# controller.net
KiCad netlist of a schematic drawn in EAGLE
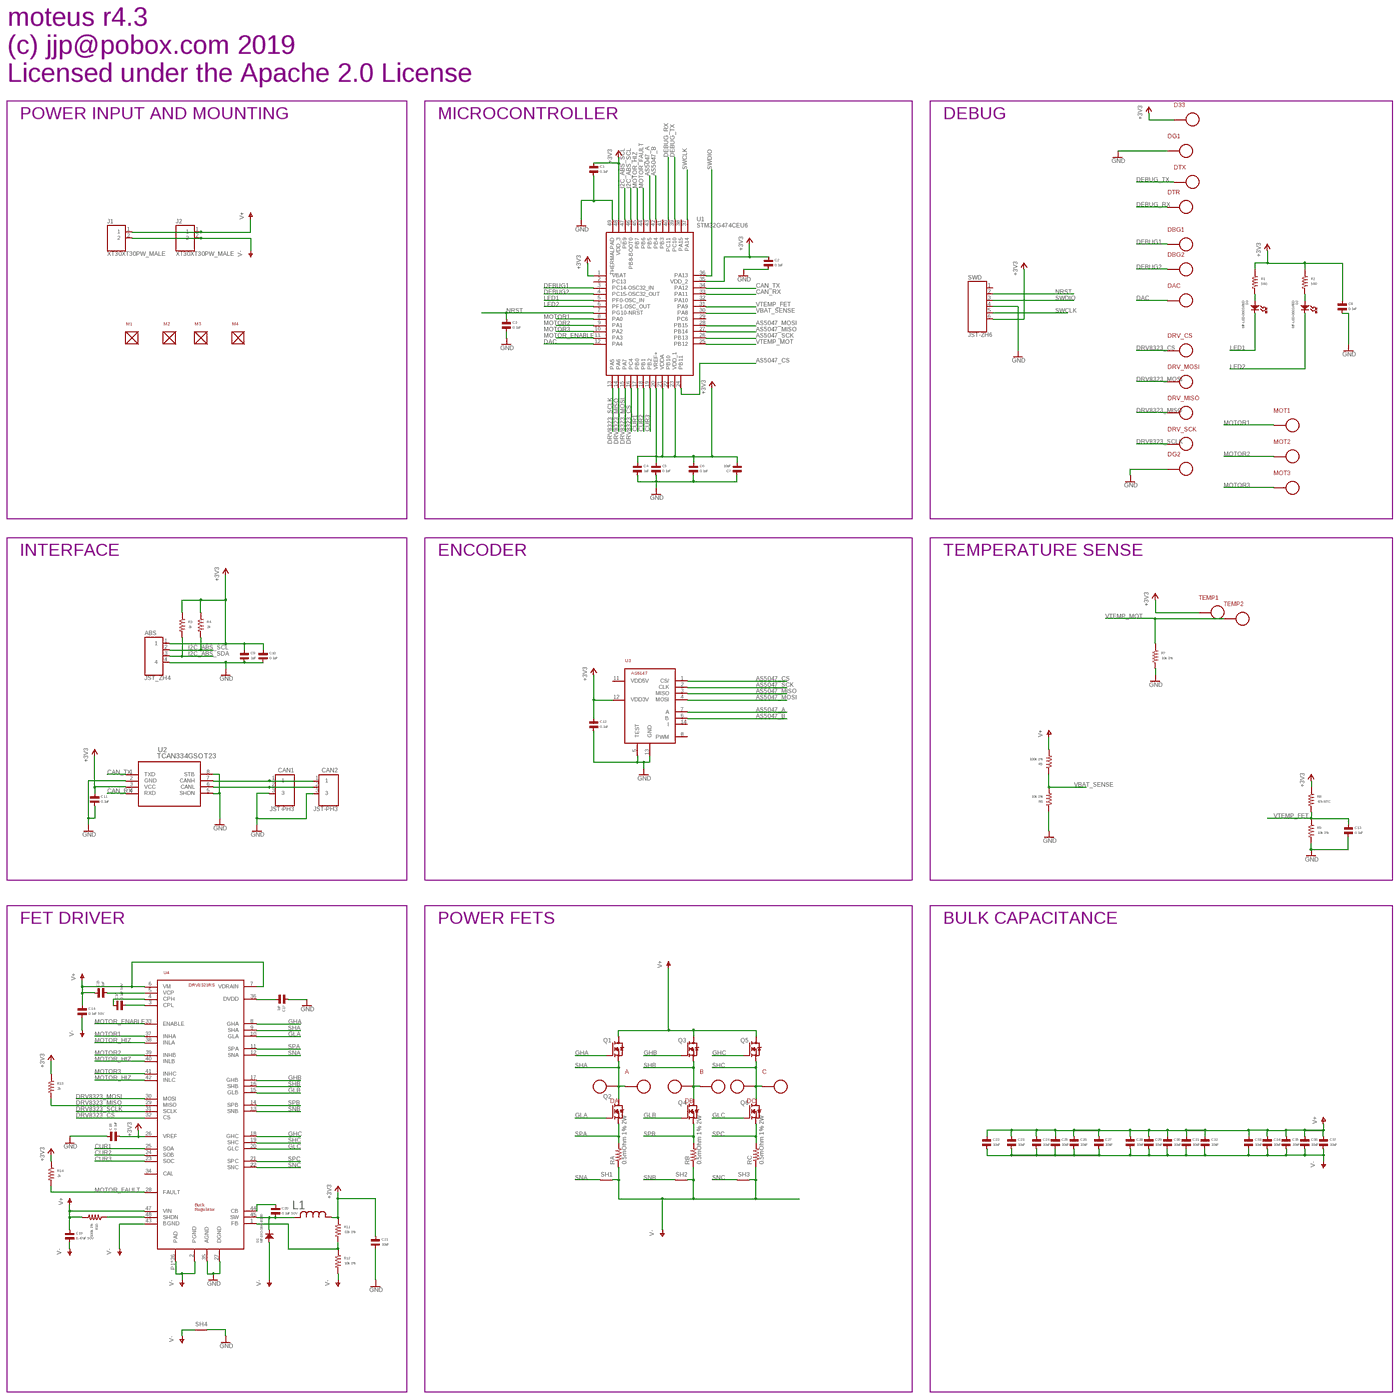
[diagram p0: schematic, sheet 1, overview]
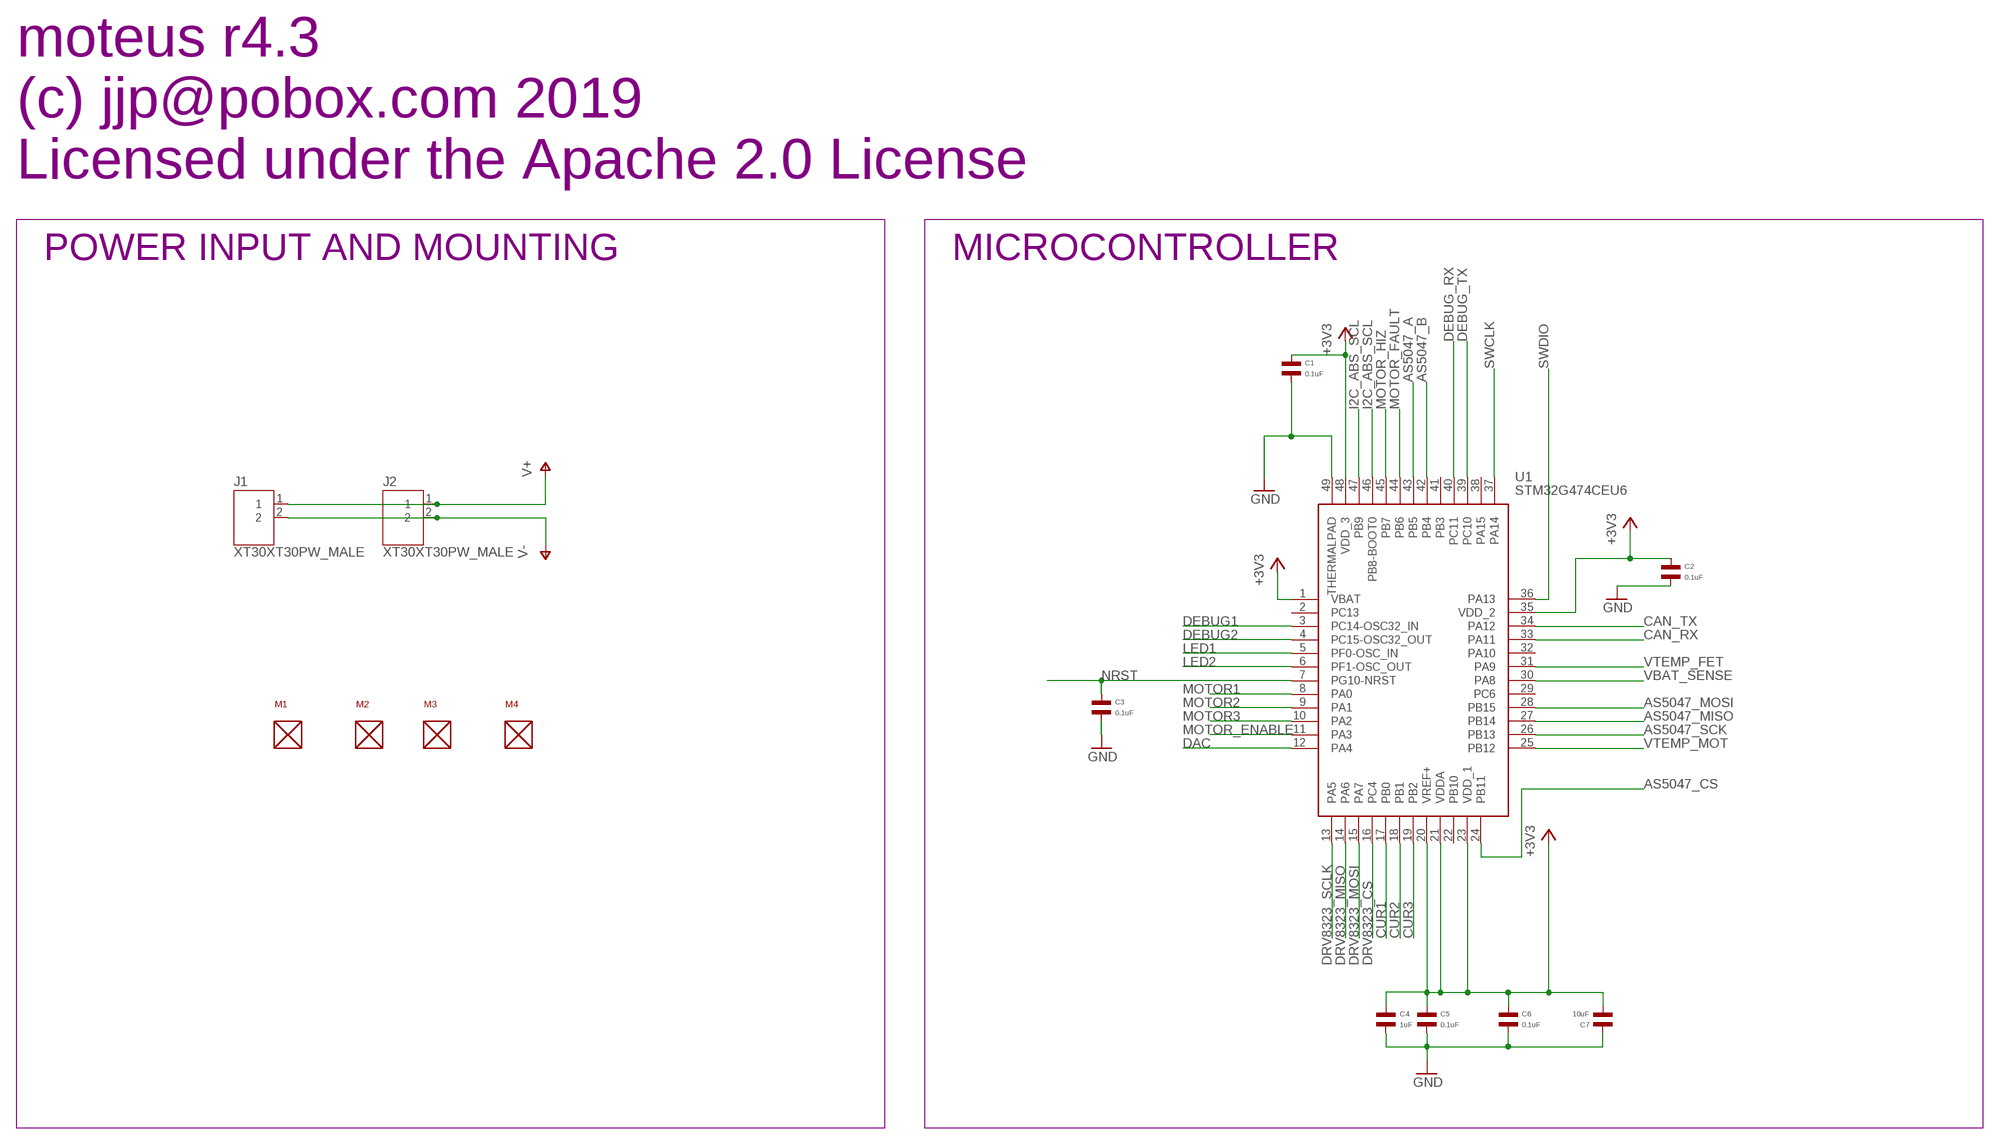
[diagram p1: schematic, sheet 1, part 1 of 4]
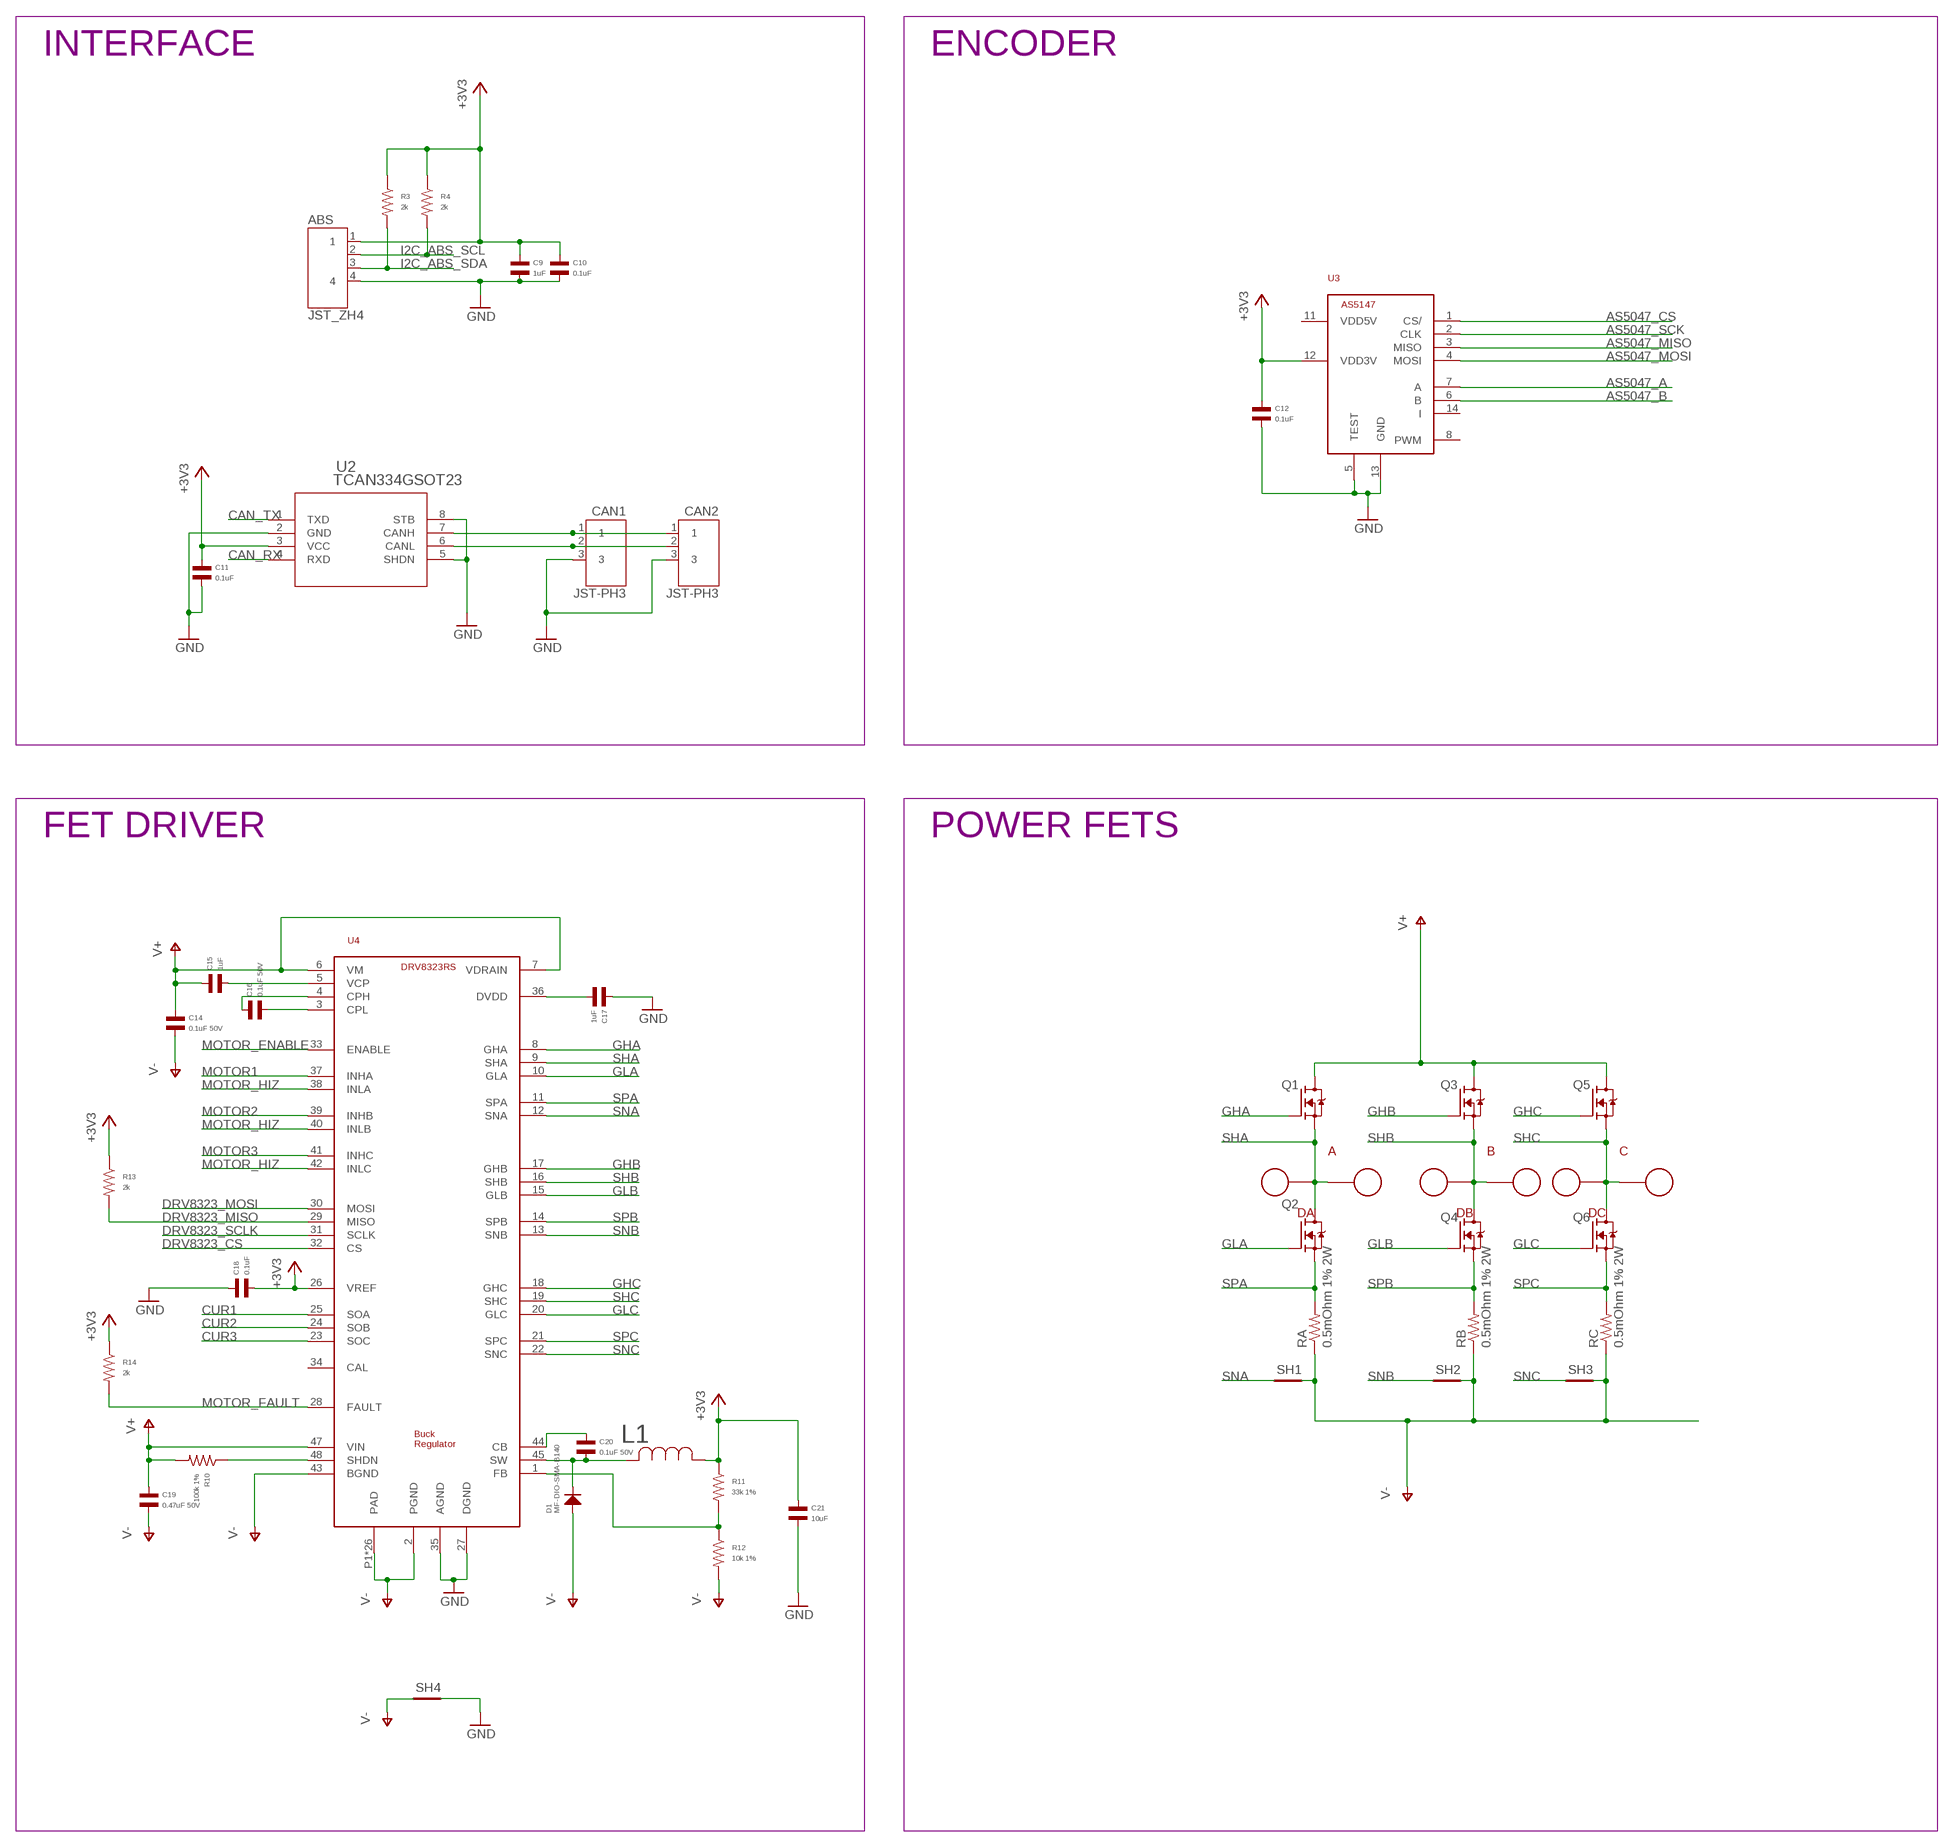
[diagram p2: schematic, sheet 1, part 2 of 4]
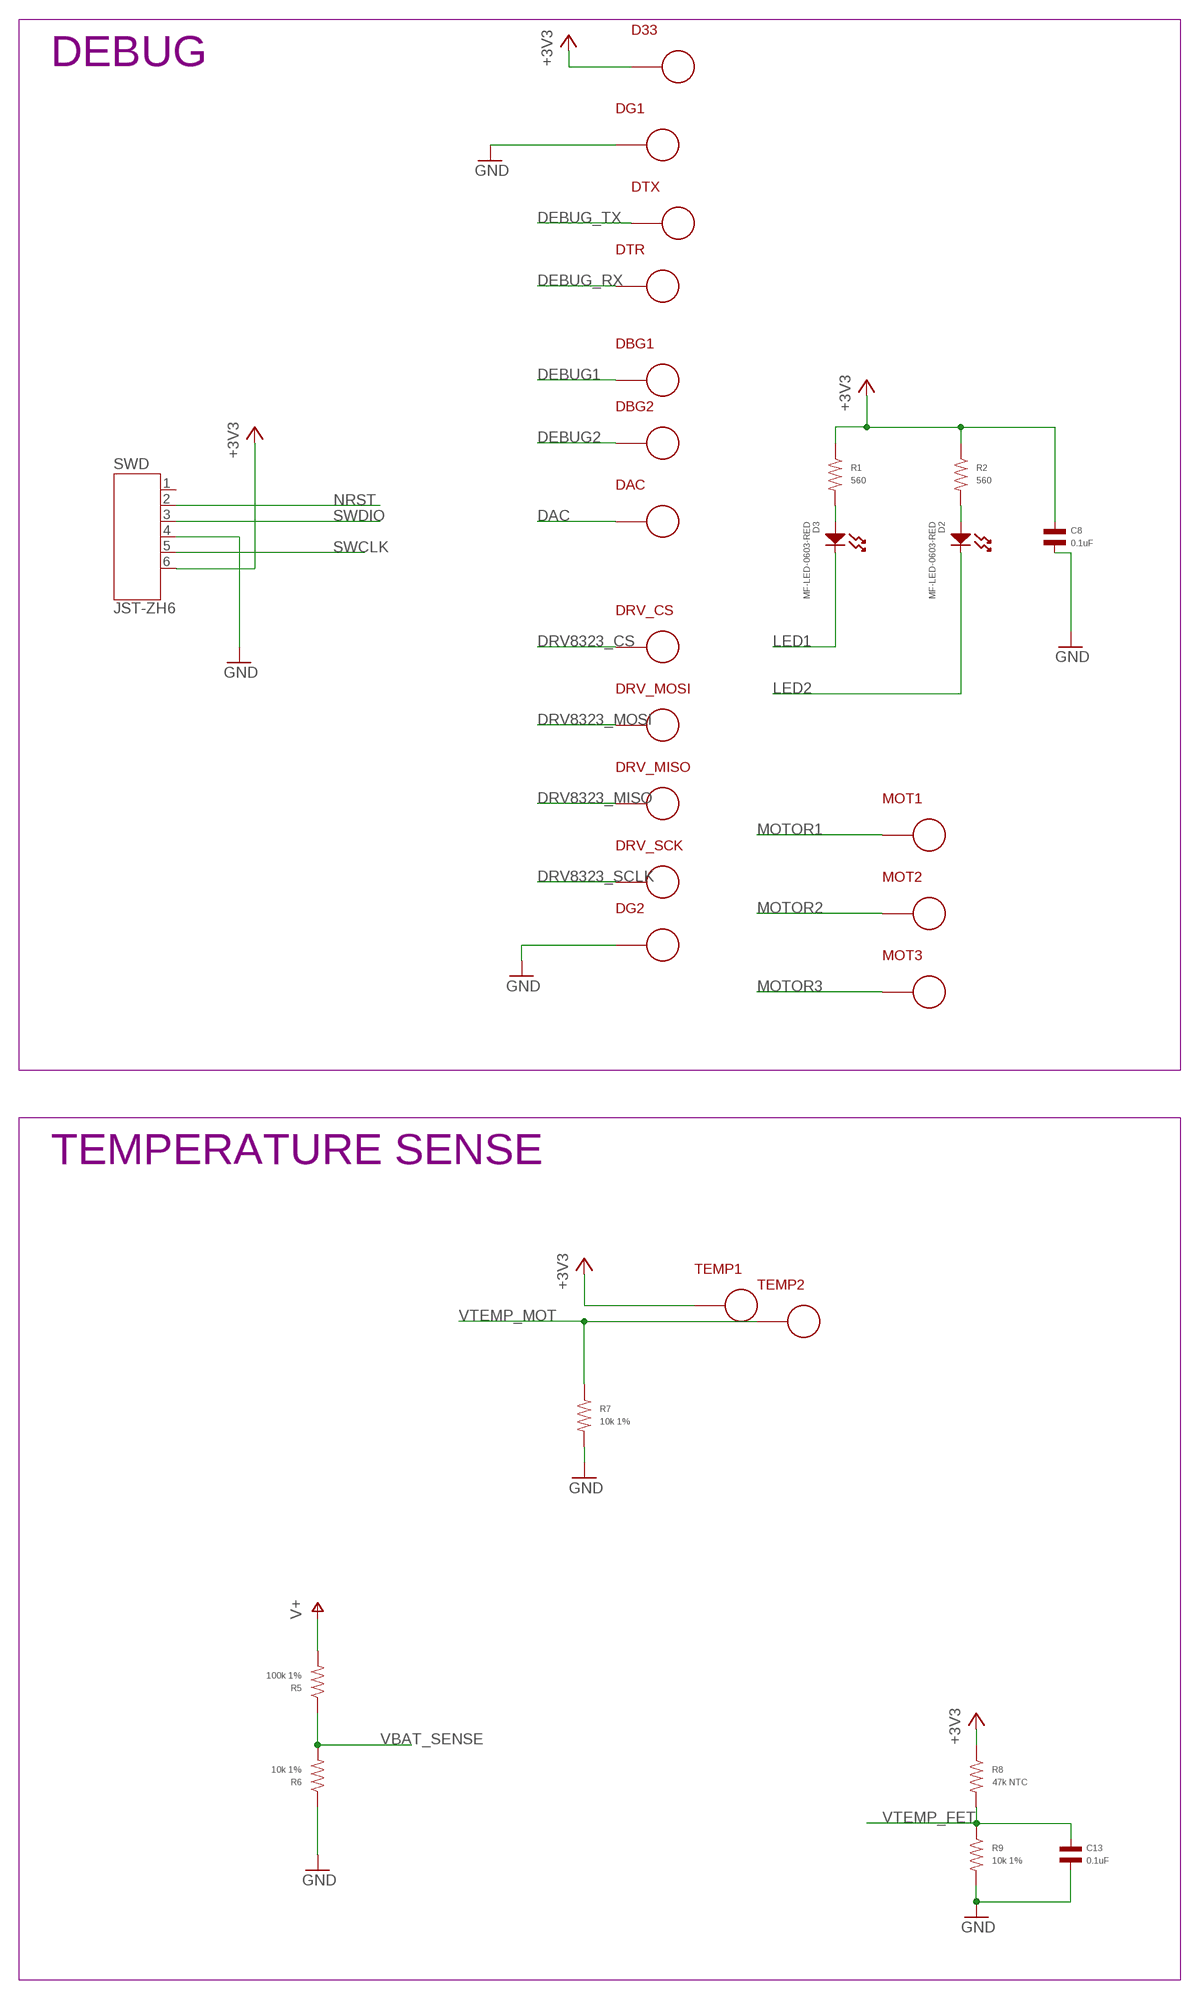
[diagram p3: schematic, sheet 1, part 3 of 4]
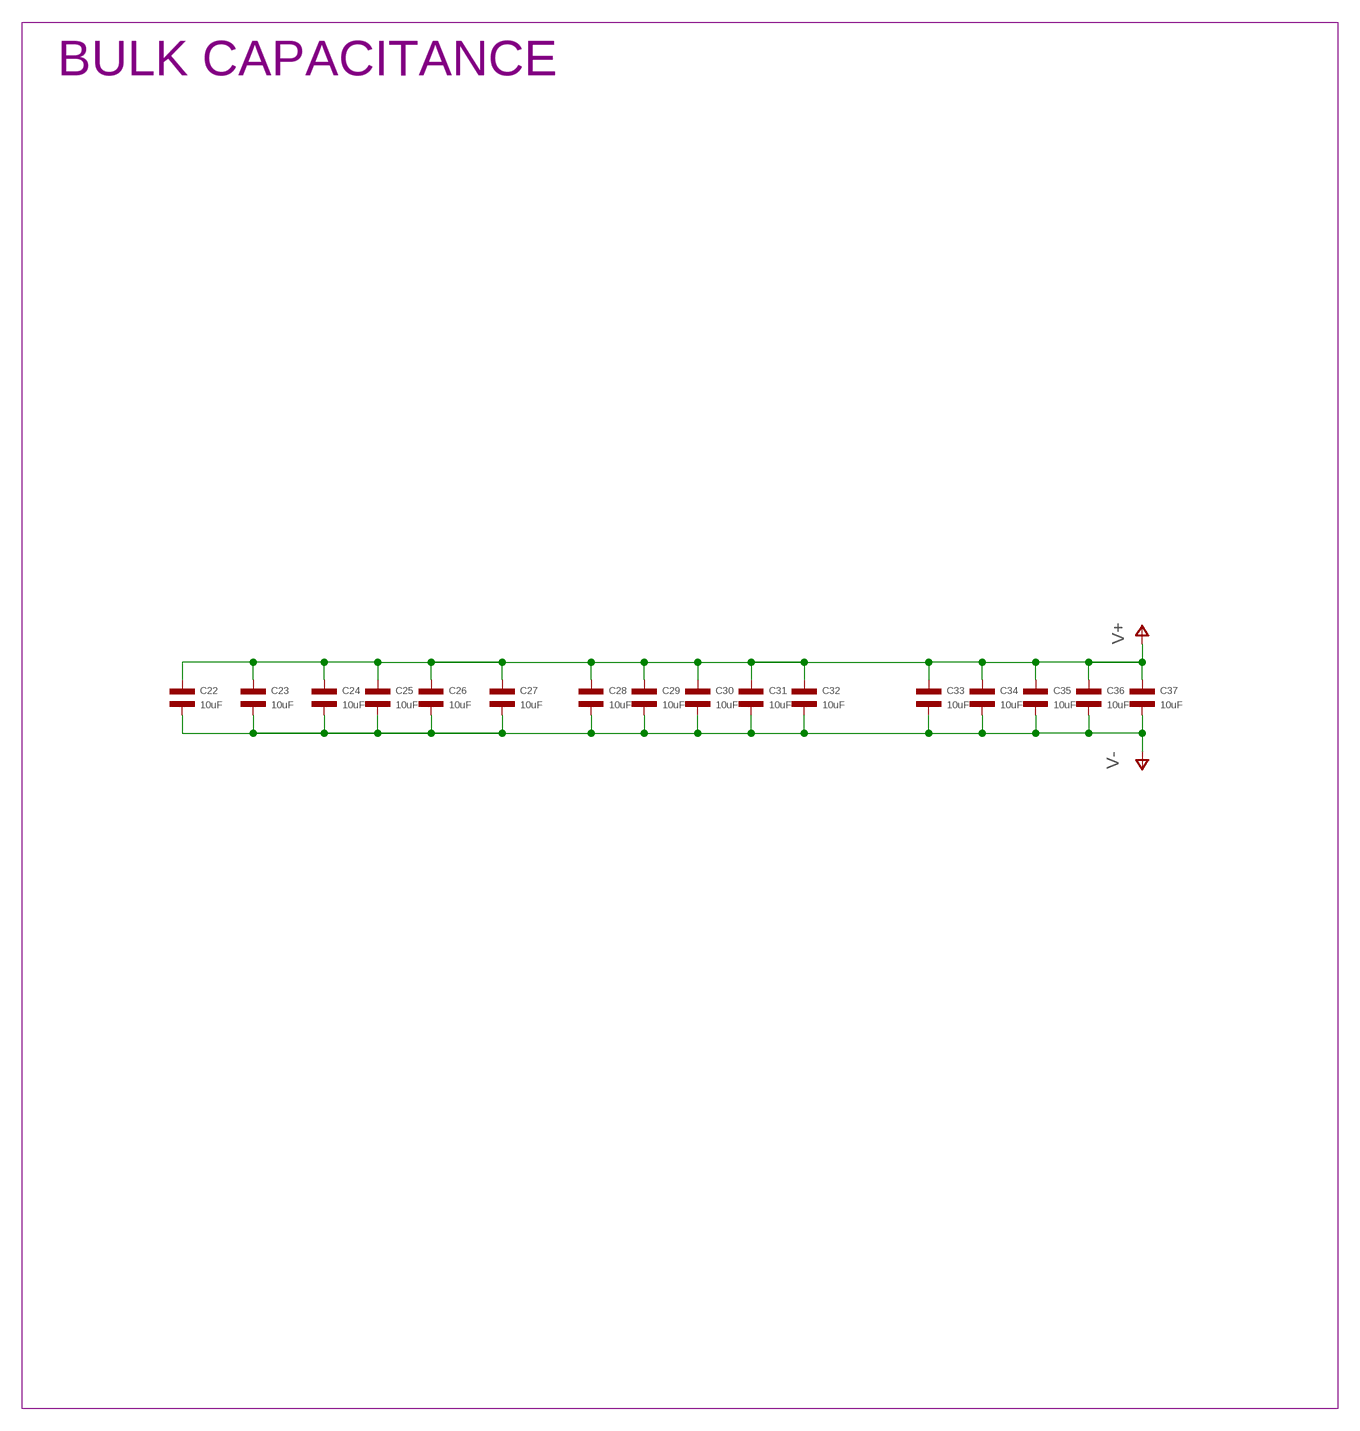
[diagram p4: schematic, sheet 1, part 4 of 4]

(export (version "E")
  (design (tool "Eeschema 10.0.6"))
  (components
    (comp (ref "A")
      (value "PAD")
      (footprint "eagle-import:18AWG_PAD")
      (libsource (lib "eagle-import") (part "PAD"))
    )
    (comp (ref "ABS")
      (value "JST_ZH4")
      (footprint "eagle-import:JST_S4B-ZR-SM4A-TF(LF)(SN)")
      (fields (field (name "MF") "JST") (field (name "MPN") "S4B-ZR-SM4A-TF(LF)(SN)"))
      (libsource (lib "eagle-import") (part "JST_ZH4"))
    )
    (comp (ref "B")
      (value "PAD")
      (footprint "eagle-import:18AWG_PAD")
      (libsource (lib "eagle-import") (part "PAD"))
    )
    (comp (ref "C")
      (value "PAD")
      (footprint "eagle-import:18AWG_PAD")
      (libsource (lib "eagle-import") (part "PAD"))
    )
    (comp (ref "C1")
      (value "0.1uF")
      (footprint "eagle-import:C0402")
      (fields (field (name "HOUSEPART") "YES") (field (name "MPN") "MF-CAP-0402-0.1uF"))
      (libsource (lib "eagle-import") (part "CAPACITOR_NP_0402"))
    )
    (comp (ref "C2")
      (value "0.1uF")
      (footprint "eagle-import:C0402")
      (fields (field (name "HOUSEPART") "YES") (field (name "MPN") "MF-CAP-0402-0.1uF"))
      (libsource (lib "eagle-import") (part "CAPACITOR_NP_0402"))
    )
    (comp (ref "C3")
      (value "0.1uF")
      (footprint "eagle-import:C0402")
      (fields (field (name "HOUSEPART") "YES") (field (name "MPN") "MF-CAP-0402-0.1uF"))
      (libsource (lib "eagle-import") (part "CAPACITOR_NP_0402"))
    )
    (comp (ref "C4")
      (value "1uF")
      (footprint "eagle-import:C0402")
      (fields (field (name "HOUSEPART") "YES") (field (name "MPN") "MF-CAP-0402-1uF"))
      (libsource (lib "eagle-import") (part "CAPACITOR_NP_0402"))
    )
    (comp (ref "C5")
      (value "0.1uF")
      (footprint "eagle-import:C0402")
      (fields (field (name "HOUSEPART") "YES") (field (name "MPN") "MF-CAP-0402-0.1uF"))
      (libsource (lib "eagle-import") (part "CAPACITOR_NP_0402"))
    )
    (comp (ref "C6")
      (value "0.1uF")
      (footprint "eagle-import:C0402")
      (fields (field (name "HOUSEPART") "YES") (field (name "MPN") "MF-CAP-0402-0.1uF"))
      (libsource (lib "eagle-import") (part "CAPACITOR_NP_0402"))
    )
    (comp (ref "C7")
      (value "10uF")
      (footprint "eagle-import:C1206")
      (fields (field (name "HOUSEPART") "YES") (field (name "MPN") "MF-CAP-1206-10uF"))
      (libsource (lib "eagle-import") (part "CAPACITOR_NP_1206"))
    )
    (comp (ref "C8")
      (value "0.1uF")
      (footprint "eagle-import:C0402")
      (fields (field (name "HOUSEPART") "YES") (field (name "MPN") "MF-CAP-0402-0.1uF"))
      (libsource (lib "eagle-import") (part "CAPACITOR_NP_0402"))
    )
    (comp (ref "C9")
      (value "1uF")
      (footprint "eagle-import:C0402")
      (fields (field (name "HOUSEPART") "YES") (field (name "MPN") "MF-CAP-0402-1uF"))
      (libsource (lib "eagle-import") (part "CAPACITOR_NP_0402"))
    )
    (comp (ref "C10")
      (value "0.1uF")
      (footprint "eagle-import:C0402")
      (fields (field (name "HOUSEPART") "YES") (field (name "MPN") "MF-CAP-0402-0.1uF"))
      (libsource (lib "eagle-import") (part "CAPACITOR_NP_0402"))
    )
    (comp (ref "C11")
      (value "0.1uF")
      (footprint "eagle-import:C0402")
      (fields (field (name "HOUSEPART") "YES") (field (name "MPN") "MF-CAP-0402-0.1uF"))
      (libsource (lib "eagle-import") (part "CAPACITOR_NP_0402"))
    )
    (comp (ref "C12")
      (value "0.1uF")
      (footprint "eagle-import:C0402")
      (fields (field (name "HOUSEPART") "YES") (field (name "MPN") "MF-CAP-0402-0.1uF"))
      (libsource (lib "eagle-import") (part "CAPACITOR_NP_0402"))
    )
    (comp (ref "C13")
      (value "0.1uF")
      (footprint "eagle-import:C0402")
      (fields (field (name "HOUSEPART") "YES") (field (name "MPN") "MF-CAP-0402-0.1uF"))
      (libsource (lib "eagle-import") (part "CAPACITOR_NP_0402"))
    )
    (comp (ref "C14")
      (value "0.1uF 50V")
      (footprint "eagle-import:C0402")
      (fields (field (name "MF") "TDK") (field (name "MPN") "CGA2B3X7R1H104K050BB"))
      (libsource (lib "eagle-import") (part "CAPACITOR_NP_0402"))
    )
    (comp (ref "C15")
      (value "1uF")
      (footprint "eagle-import:C0402")
      (fields (field (name "HOUSEPART") "YES") (field (name "MPN") "MF-CAP-0402-1uF"))
      (libsource (lib "eagle-import") (part "CAPACITOR_NP_0402"))
    )
    (comp (ref "C16")
      (value "0.1uF 50V")
      (footprint "eagle-import:C0402")
      (fields (field (name "MF") "TDK") (field (name "MPN") "CGA2B3X7R1H104K050BB"))
      (libsource (lib "eagle-import") (part "CAPACITOR_NP_0402"))
    )
    (comp (ref "C17")
      (value "1uF")
      (footprint "eagle-import:C0402")
      (fields (field (name "HOUSEPART") "YES") (field (name "MPN") "MF-CAP-0402-1uF"))
      (libsource (lib "eagle-import") (part "CAPACITOR_NP_0402"))
    )
    (comp (ref "C18")
      (value "0.1uF")
      (footprint "eagle-import:C0402")
      (fields (field (name "HOUSEPART") "YES") (field (name "MPN") "MF-CAP-0402-0.1uF"))
      (libsource (lib "eagle-import") (part "CAPACITOR_NP_0402"))
    )
    (comp (ref "C19")
      (value "0.47uF 50V")
      (footprint "eagle-import:C0402")
      (fields (field (name "MF") "Taiyo Yuden") (field (name "MPN") "UMK105ABJ474KV-F"))
      (libsource (lib "eagle-import") (part "CAPACITOR_NP_0402"))
    )
    (comp (ref "C20")
      (value "0.1uF 50V")
      (footprint "eagle-import:C0402")
      (fields (field (name "MF") "TDK") (field (name "MPN") "CGA2B3X7R1H104K050BB"))
      (libsource (lib "eagle-import") (part "CAPACITOR_NP_0402"))
    )
    (comp (ref "C21")
      (value "10uF")
      (footprint "eagle-import:C1206")
      (fields (field (name "HOUSEPART") "YES") (field (name "MPN") "MF-CAP-1206-10uF"))
      (libsource (lib "eagle-import") (part "CAPACITOR_NP_1206"))
    )
    (comp (ref "C22")
      (value "10uF")
      (footprint "eagle-import:C1206")
      (fields (field (name "MF") "TDK") (field (name "MPN") "CGA5L1X7R1H106K160AC"))
      (libsource (lib "eagle-import") (part "CAPACITOR_NP_1206"))
    )
    (comp (ref "C23")
      (value "10uF")
      (footprint "eagle-import:C1206")
      (fields (field (name "MF") "TDK") (field (name "MPN") "CGA5L1X7R1H106K160AC"))
      (libsource (lib "eagle-import") (part "CAPACITOR_NP_1206"))
    )
    (comp (ref "C24")
      (value "10uF")
      (footprint "eagle-import:C1206")
      (fields (field (name "MF") "TDK") (field (name "MPN") "CGA5L1X7R1H106K160AC"))
      (libsource (lib "eagle-import") (part "CAPACITOR_NP_1206"))
    )
    (comp (ref "C25")
      (value "10uF")
      (footprint "eagle-import:C1206")
      (fields (field (name "MF") "TDK") (field (name "MPN") "CGA5L1X7R1H106K160AC"))
      (libsource (lib "eagle-import") (part "CAPACITOR_NP_1206"))
    )
    (comp (ref "C26")
      (value "10uF")
      (footprint "eagle-import:C1206")
      (fields (field (name "MF") "TDK") (field (name "MPN") "CGA5L1X7R1H106K160AC"))
      (libsource (lib "eagle-import") (part "CAPACITOR_NP_1206"))
    )
    (comp (ref "C27")
      (value "10uF")
      (footprint "eagle-import:C1206")
      (fields (field (name "MF") "TDK") (field (name "MPN") "CGA5L1X7R1H106K160AC"))
      (libsource (lib "eagle-import") (part "CAPACITOR_NP_1206"))
    )
    (comp (ref "C28")
      (value "10uF")
      (footprint "eagle-import:C1206")
      (fields (field (name "MF") "TDK") (field (name "MPN") "CGA5L1X7R1H106K160AC"))
      (libsource (lib "eagle-import") (part "CAPACITOR_NP_1206"))
    )
    (comp (ref "C29")
      (value "10uF")
      (footprint "eagle-import:C1206")
      (fields (field (name "MF") "TDK") (field (name "MPN") "CGA5L1X7R1H106K160AC"))
      (libsource (lib "eagle-import") (part "CAPACITOR_NP_1206"))
    )
    (comp (ref "C30")
      (value "10uF")
      (footprint "eagle-import:C1206")
      (fields (field (name "MF") "TDK") (field (name "MPN") "CGA5L1X7R1H106K160AC"))
      (libsource (lib "eagle-import") (part "CAPACITOR_NP_1206"))
    )
    (comp (ref "C31")
      (value "10uF")
      (footprint "eagle-import:C1206")
      (fields (field (name "MF") "TDK") (field (name "MPN") "CGA5L1X7R1H106K160AC"))
      (libsource (lib "eagle-import") (part "CAPACITOR_NP_1206"))
    )
    (comp (ref "C32")
      (value "10uF")
      (footprint "eagle-import:C1206")
      (fields (field (name "MF") "TDK") (field (name "MPN") "CGA5L1X7R1H106K160AC"))
      (libsource (lib "eagle-import") (part "CAPACITOR_NP_1206"))
    )
    (comp (ref "C33")
      (value "10uF")
      (footprint "eagle-import:C1206")
      (fields (field (name "MF") "TDK") (field (name "MPN") "CGA5L1X7R1H106K160AC"))
      (libsource (lib "eagle-import") (part "CAPACITOR_NP_1206"))
    )
    (comp (ref "C34")
      (value "10uF")
      (footprint "eagle-import:C1206")
      (fields (field (name "MF") "TDK") (field (name "MPN") "CGA5L1X7R1H106K160AC"))
      (libsource (lib "eagle-import") (part "CAPACITOR_NP_1206"))
    )
    (comp (ref "C35")
      (value "10uF")
      (footprint "eagle-import:C1206")
      (fields (field (name "MF") "TDK") (field (name "MPN") "CGA5L1X7R1H106K160AC"))
      (libsource (lib "eagle-import") (part "CAPACITOR_NP_1206"))
    )
    (comp (ref "C36")
      (value "10uF")
      (footprint "eagle-import:C1206")
      (fields (field (name "MF") "TDK") (field (name "MPN") "CGA5L1X7R1H106K160AC"))
      (libsource (lib "eagle-import") (part "CAPACITOR_NP_1206"))
    )
    (comp (ref "C37")
      (value "10uF")
      (footprint "eagle-import:C1206")
      (fields (field (name "MF") "TDK") (field (name "MPN") "CGA5L1X7R1H106K160AC"))
      (libsource (lib "eagle-import") (part "CAPACITOR_NP_1206"))
    )
    (comp (ref "CAN1")
      (value "JST-PH3")
      (footprint "eagle-import:JST_S3B-PH-SM4-TB(LF)(SN)")
      (fields (field (name "MF") "JST") (field (name "MPN") "S3B-PH-SM4-TB(LF)(SN)"))
      (libsource (lib "eagle-import") (part "JST-PH3"))
    )
    (comp (ref "CAN2")
      (value "JST-PH3")
      (footprint "eagle-import:JST_S3B-PH-SM4-TB(LF)(SN)")
      (fields (field (name "MF") "JST") (field (name "MPN") "S3B-PH-SM4-TB(LF)(SN)"))
      (libsource (lib "eagle-import") (part "JST-PH3"))
    )
    (comp (ref "D1")
      (value "MF-DIO-SMA-B140")
      (footprint "eagle-import:SMA")
      (fields (field (name "HOUSEPART") "YES"))
      (libsource (lib "eagle-import") (part "DIODES_SMA_B140"))
    )
    (comp (ref "D2")
      (value "MF-LED-0603-RED")
      (footprint "eagle-import:LED0603")
      (fields (field (name "HOUSEPART") "YES") (field (name "MPN") "MF-LED-0603-GREEN"))
      (libsource (lib "eagle-import") (part "LED_SINGLE-0603-RED"))
    )
    (comp (ref "D3")
      (value "MF-LED-0603-RED")
      (footprint "eagle-import:LED0603")
      (fields (field (name "HOUSEPART") "YES"))
      (libsource (lib "eagle-import") (part "LED_SINGLE-0603-RED"))
    )
    (comp (ref "D33")
      (value "PAD24AWG_PAD")
      (footprint "eagle-import:24AWG_PAD")
      (libsource (lib "eagle-import") (part "PAD24AWG_PAD"))
    )
    (comp (ref "DA")
      (value "PAD24AWG_PAD")
      (footprint "eagle-import:24AWG_PAD")
      (libsource (lib "eagle-import") (part "PAD24AWG_PAD"))
    )
    (comp (ref "DAC")
      (value "PAD24AWG_PAD")
      (footprint "eagle-import:24AWG_PAD")
      (libsource (lib "eagle-import") (part "PAD24AWG_PAD"))
    )
    (comp (ref "DB")
      (value "PAD24AWG_PAD")
      (footprint "eagle-import:24AWG_PAD")
      (libsource (lib "eagle-import") (part "PAD24AWG_PAD"))
    )
    (comp (ref "DBG1")
      (value "PAD24AWG_PAD")
      (footprint "eagle-import:24AWG_PAD")
      (libsource (lib "eagle-import") (part "PAD24AWG_PAD"))
    )
    (comp (ref "DBG2")
      (value "PAD24AWG_PAD")
      (footprint "eagle-import:24AWG_PAD")
      (libsource (lib "eagle-import") (part "PAD24AWG_PAD"))
    )
    (comp (ref "DC")
      (value "PAD24AWG_PAD")
      (footprint "eagle-import:24AWG_PAD")
      (libsource (lib "eagle-import") (part "PAD24AWG_PAD"))
    )
    (comp (ref "DG1")
      (value "PAD24AWG_PAD")
      (footprint "eagle-import:24AWG_PAD")
      (libsource (lib "eagle-import") (part "PAD24AWG_PAD"))
    )
    (comp (ref "DG2")
      (value "PAD24AWG_PAD")
      (footprint "eagle-import:24AWG_PAD")
      (libsource (lib "eagle-import") (part "PAD24AWG_PAD"))
    )
    (comp (ref "DRV_CS")
      (value "PAD24AWG_PAD")
      (footprint "eagle-import:24AWG_PAD")
      (libsource (lib "eagle-import") (part "PAD24AWG_PAD"))
    )
    (comp (ref "DRV_MISO")
      (value "PAD24AWG_PAD")
      (footprint "eagle-import:24AWG_PAD")
      (libsource (lib "eagle-import") (part "PAD24AWG_PAD"))
    )
    (comp (ref "DRV_MOSI")
      (value "PAD24AWG_PAD")
      (footprint "eagle-import:24AWG_PAD")
      (libsource (lib "eagle-import") (part "PAD24AWG_PAD"))
    )
    (comp (ref "DRV_SCK")
      (value "PAD24AWG_PAD")
      (footprint "eagle-import:24AWG_PAD")
      (libsource (lib "eagle-import") (part "PAD24AWG_PAD"))
    )
    (comp (ref "DTR")
      (value "PAD24AWG_PAD")
      (footprint "eagle-import:24AWG_PAD")
      (libsource (lib "eagle-import") (part "PAD24AWG_PAD"))
    )
    (comp (ref "DTX")
      (value "PAD24AWG_PAD")
      (footprint "eagle-import:24AWG_PAD")
      (libsource (lib "eagle-import") (part "PAD24AWG_PAD"))
    )
    (comp (ref "J1")
      (value "XT30XT30PW_MALE")
      (footprint "eagle-import:XT30PW_MALE")
      (libsource (lib "eagle-import") (part "XT30XT30PW_MALE"))
    )
    (comp (ref "J2")
      (value "XT30XT30PW_MALE")
      (footprint "eagle-import:XT30PW_MALE")
      (libsource (lib "eagle-import") (part "XT30XT30PW_MALE"))
    )
    (comp (ref "L1")
      (value "SRN4018-220M")
      (footprint "eagle-import:IND_BOURNS_SRN4018")
      (fields (field (name "MANUFACTURER_PART_NUMBER") "SRN4018220M"))
      (libsource (lib "eagle-import") (part "SRN4018-220M"))
    )
    (comp (ref "M1")
      (value "MOUNT")
      (footprint "eagle-import:M2.5MOUNT")
      (libsource (lib "eagle-import") (part "MOUNT"))
    )
    (comp (ref "M2")
      (value "MOUNT")
      (footprint "eagle-import:M2.5MOUNT")
      (libsource (lib "eagle-import") (part "MOUNT"))
    )
    (comp (ref "M3")
      (value "MOUNT")
      (footprint "eagle-import:M2.5MOUNT")
      (libsource (lib "eagle-import") (part "MOUNT"))
    )
    (comp (ref "M4")
      (value "MOUNT")
      (footprint "eagle-import:M2.5MOUNT")
      (libsource (lib "eagle-import") (part "MOUNT"))
    )
    (comp (ref "MOT1")
      (value "PAD24AWG_PAD")
      (footprint "eagle-import:24AWG_PAD")
      (libsource (lib "eagle-import") (part "PAD24AWG_PAD"))
    )
    (comp (ref "MOT2")
      (value "PAD24AWG_PAD")
      (footprint "eagle-import:24AWG_PAD")
      (libsource (lib "eagle-import") (part "PAD24AWG_PAD"))
    )
    (comp (ref "MOT3")
      (value "PAD24AWG_PAD")
      (footprint "eagle-import:24AWG_PAD")
      (libsource (lib "eagle-import") (part "PAD24AWG_PAD"))
    )
    (comp (ref "Q1")
      (value "TPH1R204PLSOP_ADVANCE_8")
      (footprint "eagle-import:SOP_ADVANCE_8")
      (fields
        (field (name "MF") "Toshiba")
        (field (name "MPN") "TPH1R204PL")
        (field (name "MF_1") "Toshiba")
        (field (name "MPN_1") "TPH1R204PL,L1Q")
      )
      (libsource (lib "eagle-import") (part "TPH1R204PLSOP_ADVANCE_8"))
    )
    (comp (ref "Q2")
      (value "TPH1R204PLSOP_ADVANCE_8")
      (footprint "eagle-import:SOP_ADVANCE_8")
      (fields
        (field (name "MF") "Toshiba")
        (field (name "MPN") "TPH1R204PL")
        (field (name "MF_1") "Toshiba")
        (field (name "MPN_1") "TPH1R204PL,L1Q")
      )
      (libsource (lib "eagle-import") (part "TPH1R204PLSOP_ADVANCE_8"))
    )
    (comp (ref "Q3")
      (value "TPH1R204PLSOP_ADVANCE_8")
      (footprint "eagle-import:SOP_ADVANCE_8")
      (fields
        (field (name "MF") "Toshiba")
        (field (name "MPN") "TPH1R204PL")
        (field (name "MF_1") "Toshiba")
        (field (name "MPN_1") "TPH1R204PL,L1Q")
      )
      (libsource (lib "eagle-import") (part "TPH1R204PLSOP_ADVANCE_8"))
    )
    (comp (ref "Q4")
      (value "TPH1R204PLSOP_ADVANCE_8")
      (footprint "eagle-import:SOP_ADVANCE_8")
      (fields
        (field (name "MF") "Toshiba")
        (field (name "MPN") "TPH1R204PL")
        (field (name "MF_1") "Toshiba")
        (field (name "MPN_1") "TPH1R204PL,L1Q")
      )
      (libsource (lib "eagle-import") (part "TPH1R204PLSOP_ADVANCE_8"))
    )
    (comp (ref "Q5")
      (value "TPH1R204PLSOP_ADVANCE_8")
      (footprint "eagle-import:SOP_ADVANCE_8")
      (fields
        (field (name "MF") "Toshiba")
        (field (name "MPN") "TPH1R204PL")
        (field (name "MF_1") "Toshiba")
        (field (name "MPN_1") "TPH1R204PL,L1Q")
      )
      (libsource (lib "eagle-import") (part "TPH1R204PLSOP_ADVANCE_8"))
    )
    (comp (ref "Q6")
      (value "TPH1R204PLSOP_ADVANCE_8")
      (footprint "eagle-import:SOP_ADVANCE_8")
      (fields
        (field (name "MF") "Toshiba")
        (field (name "MPN") "TPH1R204PL")
        (field (name "MF_1") "Toshiba")
        (field (name "MPN_1") "TPH1R204PL,L1Q")
      )
      (libsource (lib "eagle-import") (part "TPH1R204PLSOP_ADVANCE_8"))
    )
    (comp (ref "R1")
      (value "560")
      (footprint "eagle-import:R0402")
      (fields (field (name "HOUSEPART") "1") (field (name "MPN") "MF-RES-0402-560"))
      (libsource (lib "eagle-import") (part "RESISTOR_0402"))
    )
    (comp (ref "R2")
      (value "560")
      (footprint "eagle-import:R0402")
      (fields (field (name "HOUSEPART") "1") (field (name "MPN") "MF-RES-0402-560"))
      (libsource (lib "eagle-import") (part "RESISTOR_0402"))
    )
    (comp (ref "R3")
      (value "2k")
      (footprint "eagle-import:R0402")
      (fields (field (name "HOUSEPART") "YES") (field (name "MPN") "MF-RES-0402-2K"))
      (libsource (lib "eagle-import") (part "RESISTOR_0402"))
    )
    (comp (ref "R4")
      (value "2k")
      (footprint "eagle-import:R0402")
      (fields (field (name "HOUSEPART") "YES") (field (name "MPN") "MF-RES-0402-2K"))
      (libsource (lib "eagle-import") (part "RESISTOR_0402"))
    )
    (comp (ref "R5")
      (value "100k 1%")
      (footprint "eagle-import:R0402")
      (fields (field (name "MF") "Panasonic") (field (name "MPN") "ERJ-2RKF1003X"))
      (libsource (lib "eagle-import") (part "RESISTOR_0402"))
    )
    (comp (ref "R6")
      (value "10k 1%")
      (footprint "eagle-import:R0402")
      (fields (field (name "MF") "Panasonic") (field (name "MPN") "ERJ-2RKF1002X"))
      (libsource (lib "eagle-import") (part "RESISTOR_0402"))
    )
    (comp (ref "R7")
      (value "10k 1%")
      (footprint "eagle-import:R0402")
      (fields (field (name "MF") "Panasonic") (field (name "MPN") "ERJ-2RKF1002X"))
      (libsource (lib "eagle-import") (part "RESISTOR_0402"))
    )
    (comp (ref "R8")
      (value "47k NTC")
      (footprint "eagle-import:R0402")
      (fields (field (name "MF") "Murata") (field (name "MPN") "NCP15WB473F03RC"))
      (libsource (lib "eagle-import") (part "RESISTOR_0402"))
    )
    (comp (ref "R9")
      (value "10k 1%")
      (footprint "eagle-import:R0402")
      (fields (field (name "MF") "Panasonic") (field (name "MPN") "ERJ-2RKF1002X"))
      (libsource (lib "eagle-import") (part "RESISTOR_0402"))
    )
    (comp (ref "R10")
      (value "100k 1%")
      (footprint "eagle-import:R0402")
      (fields (field (name "MF") "Panasonic") (field (name "MPN") "ERJ-2RKF1003X"))
      (libsource (lib "eagle-import") (part "RESISTOR_0402"))
    )
    (comp (ref "R11")
      (value "33k 1%")
      (footprint "eagle-import:R0402")
      (fields (field (name "MF") "Panasonic") (field (name "MPN") "ERJ-2RKF3302X"))
      (libsource (lib "eagle-import") (part "RESISTOR_0402"))
    )
    (comp (ref "R12")
      (value "10k 1%")
      (footprint "eagle-import:R0402")
      (fields (field (name "MF") "Panasonic") (field (name "MPN") "ERJ-2RKF1002X"))
      (libsource (lib "eagle-import") (part "RESISTOR_0402"))
    )
    (comp (ref "R13")
      (value "2k")
      (footprint "eagle-import:R0402")
      (fields (field (name "HOUSEPART") "YES") (field (name "MPN") "MF-RES-0402-2K"))
      (libsource (lib "eagle-import") (part "RESISTOR_0402"))
    )
    (comp (ref "R14")
      (value "2k")
      (footprint "eagle-import:R0402")
      (fields (field (name "HOUSEPART") "YES") (field (name "MPN") "MF-RES-0402-2K"))
      (libsource (lib "eagle-import") (part "RESISTOR_0402"))
    )
    (comp (ref "RA")
      (value "0.5mOhm 1% 2W")
      (footprint "eagle-import:M1206")
      (fields (field (name "MF") "Stackpole Electronics") (field (name "MPN") "HCS1206FTL500"))
      (libsource (lib "eagle-import") (part "R-US_M1206"))
    )
    (comp (ref "RB")
      (value "0.5mOhm 1% 2W")
      (footprint "eagle-import:M1206")
      (fields (field (name "MF") "Stackpole Electronics") (field (name "MPN") "HCS1206FTL500"))
      (libsource (lib "eagle-import") (part "R-US_M1206"))
    )
    (comp (ref "RC")
      (value "0.5mOhm 1% 2W")
      (footprint "eagle-import:M1206")
      (fields (field (name "MF") "Stackpole Electronics") (field (name "MPN") "HCS1206FTL500"))
      (libsource (lib "eagle-import") (part "R-US_M1206"))
    )
    (comp (ref "SH1")
      (value "SHORTT5")
      (footprint "eagle-import:SHORT_TOP-50")
      (libsource (lib "eagle-import") (part "SHORTT5"))
    )
    (comp (ref "SH2")
      (value "SHORTT5")
      (footprint "eagle-import:SHORT_TOP-50")
      (libsource (lib "eagle-import") (part "SHORTT5"))
    )
    (comp (ref "SH3")
      (value "SHORTT5")
      (footprint "eagle-import:SHORT_TOP-50")
      (libsource (lib "eagle-import") (part "SHORTT5"))
    )
    (comp (ref "SH4")
      (value "SHORTBIG")
      (footprint "eagle-import:SHORT_TOP-BIG")
      (libsource (lib "eagle-import") (part "SHORTBIG"))
    )
    (comp (ref "SWD")
      (value "JST-ZH6")
      (footprint "eagle-import:JST_S6B-ZR-SM4A-TF(LF)(SN)")
      (fields (field (name "MF") "JST") (field (name "MPN") "S6B-ZR-SM4A-TF(LF)(SN)"))
      (libsource (lib "eagle-import") (part "JST-ZH6"))
    )
    (comp (ref "TEMP1")
      (value "PAD24AWG_PAD")
      (footprint "eagle-import:24AWG_PAD")
      (libsource (lib "eagle-import") (part "PAD24AWG_PAD"))
    )
    (comp (ref "TEMP2")
      (value "PAD24AWG_PAD")
      (footprint "eagle-import:24AWG_PAD")
      (libsource (lib "eagle-import") (part "PAD24AWG_PAD"))
    )
    (comp (ref "U1")
      (value "STM32G474CEU6")
      (footprint "eagle-import:QFN50P700X700X60-49N")
      (fields (field (name "MOUSER_PART_NUMBER") "511-STM32G474CEU6"))
      (libsource (lib "eagle-import") (part "STM32G474CEU6"))
    )
    (comp (ref "U2")
      (value "TCAN334GSOT23")
      (footprint "eagle-import:SOT23-8")
      (fields (field (name "MF") "TI") (field (name "MPN") "TCAN334GDCNT"))
      (libsource (lib "eagle-import") (part "TCAN334GSOT23"))
    )
    (comp (ref "U3")
      (value "AS5147")
      (footprint "eagle-import:TSSOP14")
      (fields (field (name "MF") "AMS") (field (name "MPN") "AS5047P-ATSM"))
      (libsource (lib "eagle-import") (part "AS5147"))
    )
    (comp (ref "U4")
      (value "DRV8323RS")
      (footprint "eagle-import:PVQFN-N48")
      (fields (field (name "MF") "TI") (field (name "MPN") "DRV8323RSRGZR"))
      (libsource (lib "eagle-import") (part "DRV8323RS"))
    )
  )
  (nets
    (net (code "1") (name "+3V3") (class "Default")
      (node (ref "ABS") (pin "1") (pinfunction "1_1") (pintype "passive"))
      (node (ref "C1") (pin "P$1") (pinfunction "P$1_P$1") (pintype "passive"))
      (node (ref "C10") (pin "P$1") (pinfunction "P$1_P$1") (pintype "passive"))
      (node (ref "C11") (pin "P$1") (pinfunction "P$1_P$1") (pintype "passive"))
      (node (ref "C12") (pin "P$1") (pinfunction "P$1_P$1") (pintype "passive"))
      (node (ref "C18") (pin "P$2") (pinfunction "P$2_P$2") (pintype "passive"))
      (node (ref "C2") (pin "P$1") (pinfunction "P$1_P$1") (pintype "passive"))
      (node (ref "C21") (pin "P$1") (pinfunction "P$1_P$1") (pintype "passive"))
      (node (ref "C4") (pin "P$1") (pinfunction "P$1_P$1") (pintype "passive"))
      (node (ref "C5") (pin "P$1") (pinfunction "P$1_P$1") (pintype "passive"))
      (node (ref "C6") (pin "P$1") (pinfunction "P$1_P$1") (pintype "passive"))
      (node (ref "C7") (pin "P$2") (pinfunction "P$2_P$2") (pintype "passive"))
      (node (ref "C8") (pin "P$1") (pinfunction "P$1_P$1") (pintype "passive"))
      (node (ref "C9") (pin "P$1") (pinfunction "P$1_P$1") (pintype "passive"))
      (node (ref "D33") (pin "P$1") (pinfunction "P$1_P$1") (pintype "bidirectional"))
      (node (ref "L1") (pin "1") (pinfunction "1_1") (pintype "passive"))
      (node (ref "R1") (pin "P$1") (pinfunction "P$1_P$1") (pintype "passive"))
      (node (ref "R11") (pin "P$1") (pinfunction "P$1_P$1") (pintype "passive"))
      (node (ref "R13") (pin "P$1") (pinfunction "P$1_P$1") (pintype "passive"))
      (node (ref "R14") (pin "P$1") (pinfunction "P$1_P$1") (pintype "passive"))
      (node (ref "R2") (pin "P$1") (pinfunction "P$1_P$1") (pintype "passive"))
      (node (ref "R3") (pin "P$1") (pinfunction "P$1_P$1") (pintype "passive"))
      (node (ref "R4") (pin "P$1") (pinfunction "P$1_P$1") (pintype "passive"))
      (node (ref "R8") (pin "P$1") (pinfunction "P$1_P$1") (pintype "passive"))
      (node (ref "SWD") (pin "6") (pinfunction "6_6") (pintype "passive"))
      (node (ref "TEMP1") (pin "P$1") (pinfunction "P$1_P$1") (pintype "bidirectional"))
      (node (ref "U1") (pin "1") (pinfunction "VBAT_1") (pintype "bidirectional"))
      (node (ref "U1") (pin "20") (pinfunction "VREF+_20") (pintype "bidirectional"))
      (node (ref "U1") (pin "21") (pinfunction "VDDA_21") (pintype "bidirectional"))
      (node (ref "U1") (pin "23") (pinfunction "VDD_1_23") (pintype "bidirectional"))
      (node (ref "U1") (pin "35") (pinfunction "VDD_2_35") (pintype "bidirectional"))
      (node (ref "U1") (pin "48") (pinfunction "VDD_3_48") (pintype "bidirectional"))
      (node (ref "U2") (pin "3") (pinfunction "VCC_3") (pintype "power_in"))
      (node (ref "U3") (pin "12") (pinfunction "VDD3V_12") (pintype "bidirectional"))
      (node (ref "U4") (pin "26") (pinfunction "VREF_26") (pintype "bidirectional"))
    )
    (net (code "2") (name "/AS5047_A") (class "Default")
      (node (ref "U1") (pin "43") (pinfunction "PB5_43") (pintype "bidirectional"))
      (node (ref "U3") (pin "7") (pinfunction "A_7") (pintype "bidirectional"))
    )
    (net (code "3") (name "/AS5047_B") (class "Default")
      (node (ref "U1") (pin "42") (pinfunction "PB4_42") (pintype "bidirectional"))
      (node (ref "U3") (pin "6") (pinfunction "B_6") (pintype "bidirectional"))
    )
    (net (code "4") (name "/AS5047_CS") (class "Default")
      (node (ref "U1") (pin "24") (pinfunction "PB11_24") (pintype "bidirectional"))
      (node (ref "U3") (pin "1") (pinfunction "CS/_1") (pintype "bidirectional"))
    )
    (net (code "5") (name "/AS5047_MISO") (class "Default")
      (node (ref "U1") (pin "27") (pinfunction "PB14_27") (pintype "bidirectional"))
      (node (ref "U3") (pin "3") (pinfunction "MISO_3") (pintype "bidirectional"))
    )
    (net (code "6") (name "/AS5047_MOSI") (class "Default")
      (node (ref "U1") (pin "28") (pinfunction "PB15_28") (pintype "bidirectional"))
      (node (ref "U3") (pin "4") (pinfunction "MOSI_4") (pintype "bidirectional"))
    )
    (net (code "7") (name "/AS5047_SCK") (class "Default")
      (node (ref "U1") (pin "26") (pinfunction "PB13_26") (pintype "bidirectional"))
      (node (ref "U3") (pin "2") (pinfunction "CLK_2") (pintype "bidirectional"))
    )
    (net (code "8") (name "/CAN_RX") (class "Default")
      (node (ref "U1") (pin "33") (pinfunction "PA11_33") (pintype "bidirectional"))
      (node (ref "U2") (pin "4") (pinfunction "RXD_4") (pintype "output"))
    )
    (net (code "9") (name "/CAN_TX") (class "Default")
      (node (ref "U1") (pin "34") (pinfunction "PA12_34") (pintype "bidirectional"))
      (node (ref "U2") (pin "1") (pinfunction "TXD_1") (pintype "input"))
    )
    (net (code "10") (name "/CUR1") (class "Default")
      (node (ref "U1") (pin "17") (pinfunction "PB0_17") (pintype "bidirectional"))
      (node (ref "U4") (pin "25") (pinfunction "SOA_25") (pintype "bidirectional"))
    )
    (net (code "11") (name "/CUR2") (class "Default")
      (node (ref "U1") (pin "18") (pinfunction "PB1_18") (pintype "bidirectional"))
      (node (ref "U4") (pin "24") (pinfunction "SOB_24") (pintype "bidirectional"))
    )
    (net (code "12") (name "/CUR3") (class "Default")
      (node (ref "U1") (pin "19") (pinfunction "PB2_19") (pintype "bidirectional"))
      (node (ref "U4") (pin "23") (pinfunction "SOC_23") (pintype "bidirectional"))
    )
    (net (code "13") (name "/DAC") (class "Default")
      (node (ref "DAC") (pin "P$1") (pinfunction "P$1_P$1") (pintype "bidirectional"))
      (node (ref "U1") (pin "12") (pinfunction "PA4_12") (pintype "bidirectional"))
    )
    (net (code "14") (name "/DEBUG1") (class "Default")
      (node (ref "DBG1") (pin "P$1") (pinfunction "P$1_P$1") (pintype "bidirectional"))
      (node (ref "U1") (pin "3") (pinfunction "PC14-OSC32_IN_3") (pintype "bidirectional"))
    )
    (net (code "15") (name "/DEBUG2") (class "Default")
      (node (ref "DBG2") (pin "P$1") (pinfunction "P$1_P$1") (pintype "bidirectional"))
      (node (ref "U1") (pin "4") (pinfunction "PC15-OSC32_OUT_4") (pintype "bidirectional"))
    )
    (net (code "16") (name "/DEBUG_RX") (class "Default")
      (node (ref "DTR") (pin "P$1") (pinfunction "P$1_P$1") (pintype "bidirectional"))
      (node (ref "U1") (pin "40") (pinfunction "PC11_40") (pintype "bidirectional"))
    )
    (net (code "17") (name "/DEBUG_TX") (class "Default")
      (node (ref "DTX") (pin "P$1") (pinfunction "P$1_P$1") (pintype "bidirectional"))
      (node (ref "U1") (pin "39") (pinfunction "PC10_39") (pintype "bidirectional"))
    )
    (net (code "18") (name "/DRV8323_CS") (class "Default")
      (node (ref "DRV_CS") (pin "P$1") (pinfunction "P$1_P$1") (pintype "bidirectional"))
      (node (ref "U1") (pin "16") (pinfunction "PC4_16") (pintype "bidirectional"))
      (node (ref "U4") (pin "32") (pinfunction "CS_32") (pintype "bidirectional"))
    )
    (net (code "19") (name "/DRV8323_MISO") (class "Default")
      (node (ref "DRV_MISO") (pin "P$1") (pinfunction "P$1_P$1") (pintype "bidirectional"))
      (node (ref "R13") (pin "P$2") (pinfunction "P$2_P$2") (pintype "passive"))
      (node (ref "U1") (pin "14") (pinfunction "PA6_14") (pintype "bidirectional"))
      (node (ref "U4") (pin "29") (pinfunction "MISO_29") (pintype "bidirectional"))
    )
    (net (code "20") (name "/DRV8323_MOSI") (class "Default")
      (node (ref "DRV_MOSI") (pin "P$1") (pinfunction "P$1_P$1") (pintype "bidirectional"))
      (node (ref "U1") (pin "15") (pinfunction "PA7_15") (pintype "bidirectional"))
      (node (ref "U4") (pin "30") (pinfunction "MOSI_30") (pintype "bidirectional"))
    )
    (net (code "21") (name "/DRV8323_SCLK") (class "Default")
      (node (ref "DRV_SCK") (pin "P$1") (pinfunction "P$1_P$1") (pintype "bidirectional"))
      (node (ref "U1") (pin "13") (pinfunction "PA5_13") (pintype "bidirectional"))
      (node (ref "U4") (pin "31") (pinfunction "SCLK_31") (pintype "bidirectional"))
    )
    (net (code "22") (name "/GHA") (class "Default")
      (node (ref "Q1") (pin "4") (pinfunction "G_4") (pintype "passive"))
      (node (ref "U4") (pin "8") (pinfunction "GHA_8") (pintype "bidirectional"))
    )
    (net (code "23") (name "/GHB") (class "Default")
      (node (ref "Q3") (pin "4") (pinfunction "G_4") (pintype "passive"))
      (node (ref "U4") (pin "17") (pinfunction "GHB_17") (pintype "bidirectional"))
    )
    (net (code "24") (name "/GHC") (class "Default")
      (node (ref "Q5") (pin "4") (pinfunction "G_4") (pintype "passive"))
      (node (ref "U4") (pin "18") (pinfunction "GHC_18") (pintype "bidirectional"))
    )
    (net (code "25") (name "/GLA") (class "Default")
      (node (ref "Q2") (pin "4") (pinfunction "G_4") (pintype "passive"))
      (node (ref "U4") (pin "10") (pinfunction "GLA_10") (pintype "bidirectional"))
    )
    (net (code "26") (name "/GLB") (class "Default")
      (node (ref "Q4") (pin "4") (pinfunction "G_4") (pintype "passive"))
      (node (ref "U4") (pin "15") (pinfunction "GLB_15") (pintype "bidirectional"))
    )
    (net (code "27") (name "/GLC") (class "Default")
      (node (ref "Q6") (pin "4") (pinfunction "G_4") (pintype "passive"))
      (node (ref "U4") (pin "20") (pinfunction "GLC_20") (pintype "bidirectional"))
    )
    (net (code "28") (name "/I2C_ABS_SCL") (class "Default")
      (node (ref "ABS") (pin "2") (pinfunction "2_2") (pintype "passive"))
      (node (ref "R4") (pin "P$2") (pinfunction "P$2_P$2") (pintype "passive"))
      (node (ref "U1") (pin "46") (pinfunction "PB8-BOOT0_46") (pintype "bidirectional"))
      (node (ref "U1") (pin "47") (pinfunction "PB9_47") (pintype "bidirectional"))
    )
    (net (code "29") (name "/I2C_ABS_SDA") (class "Default")
      (node (ref "ABS") (pin "3") (pinfunction "3_3") (pintype "passive"))
      (node (ref "R3") (pin "P$2") (pinfunction "P$2_P$2") (pintype "passive"))
    )
    (net (code "30") (name "/LED1") (class "Default")
      (node (ref "D3") (pin "CATHODE") (pinfunction "CATHODE_CATHODE") (pintype "power_in"))
      (node (ref "U1") (pin "5") (pinfunction "PF0-OSC_IN_5") (pintype "bidirectional"))
    )
    (net (code "31") (name "/LED2") (class "Default")
      (node (ref "D2") (pin "CATHODE") (pinfunction "CATHODE_CATHODE") (pintype "power_in"))
      (node (ref "U1") (pin "6") (pinfunction "PF1-OSC_OUT_6") (pintype "bidirectional"))
    )
    (net (code "32") (name "/MOTOR1") (class "Default")
      (node (ref "MOT1") (pin "P$1") (pinfunction "P$1_P$1") (pintype "bidirectional"))
      (node (ref "U1") (pin "8") (pinfunction "PA0_8") (pintype "bidirectional"))
      (node (ref "U4") (pin "37") (pinfunction "INHA_37") (pintype "bidirectional"))
    )
    (net (code "33") (name "/MOTOR2") (class "Default")
      (node (ref "MOT2") (pin "P$1") (pinfunction "P$1_P$1") (pintype "bidirectional"))
      (node (ref "U1") (pin "9") (pinfunction "PA1_9") (pintype "bidirectional"))
      (node (ref "U4") (pin "39") (pinfunction "INHB_39") (pintype "bidirectional"))
    )
    (net (code "34") (name "/MOTOR3") (class "Default")
      (node (ref "MOT3") (pin "P$1") (pinfunction "P$1_P$1") (pintype "bidirectional"))
      (node (ref "U1") (pin "10") (pinfunction "PA2_10") (pintype "bidirectional"))
      (node (ref "U4") (pin "41") (pinfunction "INHC_41") (pintype "bidirectional"))
    )
    (net (code "35") (name "/MOTOR_ENABLE") (class "Default")
      (node (ref "U1") (pin "11") (pinfunction "PA3_11") (pintype "bidirectional"))
      (node (ref "U4") (pin "33") (pinfunction "ENABLE_33") (pintype "bidirectional"))
    )
    (net (code "36") (name "/MOTOR_FAULT") (class "Default")
      (node (ref "R14") (pin "P$2") (pinfunction "P$2_P$2") (pintype "passive"))
      (node (ref "U1") (pin "44") (pinfunction "PB6_44") (pintype "bidirectional"))
      (node (ref "U4") (pin "28") (pinfunction "FAULT_28") (pintype "bidirectional"))
    )
    (net (code "37") (name "/MOTOR_HIZ") (class "Default")
      (node (ref "U1") (pin "45") (pinfunction "PB7_45") (pintype "bidirectional"))
      (node (ref "U4") (pin "38") (pinfunction "INLA_38") (pintype "bidirectional"))
      (node (ref "U4") (pin "40") (pinfunction "INLB_40") (pintype "bidirectional"))
      (node (ref "U4") (pin "42") (pinfunction "INLC_42") (pintype "bidirectional"))
    )
    (net (code "38") (name "/NRST") (class "Default")
      (node (ref "C3") (pin "P$1") (pinfunction "P$1_P$1") (pintype "passive"))
      (node (ref "SWD") (pin "2") (pinfunction "2_2") (pintype "passive"))
      (node (ref "U1") (pin "7") (pinfunction "PG10-NRST_7") (pintype "bidirectional"))
    )
    (net (code "39") (name "/SHA") (class "Default")
      (node (ref "A") (pin "1") (pinfunction "P$1_1") (pintype "bidirectional"))
      (node (ref "DA") (pin "P$1") (pinfunction "P$1_P$1") (pintype "bidirectional"))
      (node (ref "Q1") (pin "1") (pinfunction "S_1") (pintype "passive"))
      (node (ref "Q1") (pin "2") (pinfunction "S_2") (pintype "passive"))
      (node (ref "Q1") (pin "3") (pinfunction "S_3") (pintype "passive"))
      (node (ref "Q2") (pin "5") (pinfunction "D_5") (pintype "passive"))
      (node (ref "Q2") (pin "6") (pinfunction "D_6") (pintype "passive"))
      (node (ref "Q2") (pin "7") (pinfunction "D_7") (pintype "passive"))
      (node (ref "Q2") (pin "8") (pinfunction "D_8") (pintype "passive"))
      (node (ref "Q2") (pin "PAD") (pinfunction "D_PAD") (pintype "passive"))
      (node (ref "U4") (pin "9") (pinfunction "SHA_9") (pintype "bidirectional"))
    )
    (net (code "40") (name "/SHB") (class "Default")
      (node (ref "B") (pin "1") (pinfunction "P$1_1") (pintype "bidirectional"))
      (node (ref "DB") (pin "P$1") (pinfunction "P$1_P$1") (pintype "bidirectional"))
      (node (ref "Q3") (pin "1") (pinfunction "S_1") (pintype "passive"))
      (node (ref "Q3") (pin "2") (pinfunction "S_2") (pintype "passive"))
      (node (ref "Q3") (pin "3") (pinfunction "S_3") (pintype "passive"))
      (node (ref "Q4") (pin "5") (pinfunction "D_5") (pintype "passive"))
      (node (ref "Q4") (pin "6") (pinfunction "D_6") (pintype "passive"))
      (node (ref "Q4") (pin "7") (pinfunction "D_7") (pintype "passive"))
      (node (ref "Q4") (pin "8") (pinfunction "D_8") (pintype "passive"))
      (node (ref "Q4") (pin "PAD") (pinfunction "D_PAD") (pintype "passive"))
      (node (ref "U4") (pin "16") (pinfunction "SHB_16") (pintype "bidirectional"))
    )
    (net (code "41") (name "/SHC") (class "Default")
      (node (ref "C") (pin "1") (pinfunction "P$1_1") (pintype "bidirectional"))
      (node (ref "DC") (pin "P$1") (pinfunction "P$1_P$1") (pintype "bidirectional"))
      (node (ref "Q5") (pin "1") (pinfunction "S_1") (pintype "passive"))
      (node (ref "Q5") (pin "2") (pinfunction "S_2") (pintype "passive"))
      (node (ref "Q5") (pin "3") (pinfunction "S_3") (pintype "passive"))
      (node (ref "Q6") (pin "5") (pinfunction "D_5") (pintype "passive"))
      (node (ref "Q6") (pin "6") (pinfunction "D_6") (pintype "passive"))
      (node (ref "Q6") (pin "7") (pinfunction "D_7") (pintype "passive"))
      (node (ref "Q6") (pin "8") (pinfunction "D_8") (pintype "passive"))
      (node (ref "Q6") (pin "PAD") (pinfunction "D_PAD") (pintype "passive"))
      (node (ref "U4") (pin "19") (pinfunction "SHC_19") (pintype "bidirectional"))
    )
    (net (code "42") (name "/SNA") (class "Default")
      (node (ref "SH1") (pin "1") (pinfunction "P$1_1") (pintype "bidirectional"))
      (node (ref "U4") (pin "12") (pinfunction "SNA_12") (pintype "bidirectional"))
    )
    (net (code "43") (name "/SNB") (class "Default")
      (node (ref "SH2") (pin "1") (pinfunction "P$1_1") (pintype "bidirectional"))
      (node (ref "U4") (pin "13") (pinfunction "SNB_13") (pintype "bidirectional"))
    )
    (net (code "44") (name "/SNC") (class "Default")
      (node (ref "SH3") (pin "1") (pinfunction "P$1_1") (pintype "bidirectional"))
      (node (ref "U4") (pin "22") (pinfunction "SNC_22") (pintype "bidirectional"))
    )
    (net (code "45") (name "/SPA") (class "Default")
      (node (ref "Q2") (pin "1") (pinfunction "S_1") (pintype "passive"))
      (node (ref "Q2") (pin "2") (pinfunction "S_2") (pintype "passive"))
      (node (ref "Q2") (pin "3") (pinfunction "S_3") (pintype "passive"))
      (node (ref "RA") (pin "2") (pinfunction "2_2") (pintype "passive"))
      (node (ref "U4") (pin "11") (pinfunction "SPA_11") (pintype "bidirectional"))
    )
    (net (code "46") (name "/SPB") (class "Default")
      (node (ref "Q4") (pin "1") (pinfunction "S_1") (pintype "passive"))
      (node (ref "Q4") (pin "2") (pinfunction "S_2") (pintype "passive"))
      (node (ref "Q4") (pin "3") (pinfunction "S_3") (pintype "passive"))
      (node (ref "RB") (pin "2") (pinfunction "2_2") (pintype "passive"))
      (node (ref "U4") (pin "14") (pinfunction "SPB_14") (pintype "bidirectional"))
    )
    (net (code "47") (name "/SPC") (class "Default")
      (node (ref "Q6") (pin "1") (pinfunction "S_1") (pintype "passive"))
      (node (ref "Q6") (pin "2") (pinfunction "S_2") (pintype "passive"))
      (node (ref "Q6") (pin "3") (pinfunction "S_3") (pintype "passive"))
      (node (ref "RC") (pin "2") (pinfunction "2_2") (pintype "passive"))
      (node (ref "U4") (pin "21") (pinfunction "SPC_21") (pintype "bidirectional"))
    )
    (net (code "48") (name "/SWCLK") (class "Default")
      (node (ref "SWD") (pin "5") (pinfunction "5_5") (pintype "passive"))
      (node (ref "U1") (pin "37") (pinfunction "PA14_37") (pintype "bidirectional"))
    )
    (net (code "49") (name "/SWDIO") (class "Default")
      (node (ref "SWD") (pin "3") (pinfunction "3_3") (pintype "passive"))
      (node (ref "U1") (pin "36") (pinfunction "PA13_36") (pintype "bidirectional"))
    )
    (net (code "50") (name "/VBAT_SENSE") (class "Default")
      (node (ref "R5") (pin "P$1") (pinfunction "P$1_P$1") (pintype "passive"))
      (node (ref "R6") (pin "P$2") (pinfunction "P$2_P$2") (pintype "passive"))
      (node (ref "U1") (pin "30") (pinfunction "PA8_30") (pintype "bidirectional"))
    )
    (net (code "51") (name "/VTEMP_FET") (class "Default")
      (node (ref "C13") (pin "P$1") (pinfunction "P$1_P$1") (pintype "passive"))
      (node (ref "R8") (pin "P$2") (pinfunction "P$2_P$2") (pintype "passive"))
      (node (ref "R9") (pin "P$1") (pinfunction "P$1_P$1") (pintype "passive"))
      (node (ref "U1") (pin "31") (pinfunction "PA9_31") (pintype "bidirectional"))
    )
    (net (code "52") (name "/VTEMP_MOT") (class "Default")
      (node (ref "R7") (pin "P$1") (pinfunction "P$1_P$1") (pintype "passive"))
      (node (ref "TEMP2") (pin "P$1") (pinfunction "P$1_P$1") (pintype "bidirectional"))
      (node (ref "U1") (pin "25") (pinfunction "PB12_25") (pintype "bidirectional"))
    )
    (net (code "53") (name "GND") (class "Default")
      (node (ref "ABS") (pin "4") (pinfunction "4_4") (pintype "passive"))
      (node (ref "C1") (pin "P$2") (pinfunction "P$2_P$2") (pintype "passive"))
      (node (ref "C10") (pin "P$2") (pinfunction "P$2_P$2") (pintype "passive"))
      (node (ref "C11") (pin "P$2") (pinfunction "P$2_P$2") (pintype "passive"))
      (node (ref "C12") (pin "P$2") (pinfunction "P$2_P$2") (pintype "passive"))
      (node (ref "C13") (pin "P$2") (pinfunction "P$2_P$2") (pintype "passive"))
      (node (ref "C17") (pin "P$1") (pinfunction "P$1_P$1") (pintype "passive"))
      (node (ref "C18") (pin "P$1") (pinfunction "P$1_P$1") (pintype "passive"))
      (node (ref "C2") (pin "P$2") (pinfunction "P$2_P$2") (pintype "passive"))
      (node (ref "C21") (pin "P$2") (pinfunction "P$2_P$2") (pintype "passive"))
      (node (ref "C3") (pin "P$2") (pinfunction "P$2_P$2") (pintype "passive"))
      (node (ref "C4") (pin "P$2") (pinfunction "P$2_P$2") (pintype "passive"))
      (node (ref "C5") (pin "P$2") (pinfunction "P$2_P$2") (pintype "passive"))
      (node (ref "C6") (pin "P$2") (pinfunction "P$2_P$2") (pintype "passive"))
      (node (ref "C7") (pin "P$1") (pinfunction "P$1_P$1") (pintype "passive"))
      (node (ref "C8") (pin "P$2") (pinfunction "P$2_P$2") (pintype "passive"))
      (node (ref "C9") (pin "P$2") (pinfunction "P$2_P$2") (pintype "passive"))
      (node (ref "CAN1") (pin "3") (pinfunction "3_3") (pintype "passive"))
      (node (ref "CAN2") (pin "3") (pinfunction "3_3") (pintype "passive"))
      (node (ref "DG1") (pin "P$1") (pinfunction "P$1_P$1") (pintype "bidirectional"))
      (node (ref "DG2") (pin "P$1") (pinfunction "P$1_P$1") (pintype "bidirectional"))
      (node (ref "R6") (pin "P$1") (pinfunction "P$1_P$1") (pintype "passive"))
      (node (ref "R7") (pin "P$2") (pinfunction "P$2_P$2") (pintype "passive"))
      (node (ref "R9") (pin "P$2") (pinfunction "P$2_P$2") (pintype "passive"))
      (node (ref "SH4") (pin "2") (pinfunction "P$2_2") (pintype "bidirectional"))
      (node (ref "SWD") (pin "4") (pinfunction "4_4") (pintype "passive"))
      (node (ref "U1") (pin "49") (pinfunction "THERMALPAD_49") (pintype "bidirectional"))
      (node (ref "U2") (pin "2") (pinfunction "GND_2") (pintype "power_in"))
      (node (ref "U2") (pin "5") (pinfunction "SHDN_5") (pintype "input"))
      (node (ref "U2") (pin "8") (pinfunction "STB_8") (pintype "input"))
      (node (ref "U3") (pin "13") (pinfunction "GND_13") (pintype "bidirectional"))
      (node (ref "U3") (pin "5") (pinfunction "TEST_5") (pintype "bidirectional"))
      (node (ref "U4") (pin "27") (pinfunction "DGND_27") (pintype "bidirectional"))
      (node (ref "U4") (pin "35") (pinfunction "AGND_35") (pintype "bidirectional"))
    )
    (net (code "54") (name "Net-(D2-PadANODE)") (class "Default")
      (node (ref "D2") (pin "ANODE") (pinfunction "ANODE_ANODE") (pintype "power_in"))
      (node (ref "R2") (pin "P$2") (pinfunction "P$2_P$2") (pintype "passive"))
    )
    (net (code "55") (name "Net-(D3-PadANODE)") (class "Default")
      (node (ref "D3") (pin "ANODE") (pinfunction "ANODE_ANODE") (pintype "power_in"))
      (node (ref "R1") (pin "P$2") (pinfunction "P$2_P$2") (pintype "passive"))
    )
    (net (code "56") (name "Net-(U2-CANH)") (class "Default")
      (node (ref "CAN1") (pin "1") (pinfunction "1_1") (pintype "passive"))
      (node (ref "CAN2") (pin "1") (pinfunction "1_1") (pintype "passive"))
      (node (ref "U2") (pin "7") (pinfunction "CANH_7") (pintype "bidirectional"))
    )
    (net (code "57") (name "Net-(U2-CANL)") (class "Default")
      (node (ref "CAN1") (pin "2") (pinfunction "2_2") (pintype "passive"))
      (node (ref "CAN2") (pin "2") (pinfunction "2_2") (pintype "passive"))
      (node (ref "U2") (pin "6") (pinfunction "CANL_6") (pintype "bidirectional"))
    )
    (net (code "58") (name "Net-(U4-CB)") (class "Default")
      (node (ref "C20") (pin "P$1") (pinfunction "P$1_P$1") (pintype "passive"))
      (node (ref "U4") (pin "44") (pinfunction "CB_44") (pintype "bidirectional"))
    )
    (net (code "59") (name "Net-(U4-CPH)") (class "Default")
      (node (ref "C16") (pin "P$1") (pinfunction "P$1_P$1") (pintype "passive"))
      (node (ref "U4") (pin "4") (pinfunction "CPH_4") (pintype "bidirectional"))
    )
    (net (code "60") (name "Net-(U4-CPL)") (class "Default")
      (node (ref "C16") (pin "P$2") (pinfunction "P$2_P$2") (pintype "passive"))
      (node (ref "U4") (pin "3") (pinfunction "CPL_3") (pintype "bidirectional"))
    )
    (net (code "61") (name "Net-(U4-DVDD)") (class "Default")
      (node (ref "C17") (pin "P$2") (pinfunction "P$2_P$2") (pintype "passive"))
      (node (ref "U4") (pin "36") (pinfunction "DVDD_36") (pintype "bidirectional"))
    )
    (net (code "62") (name "Net-(U4-FB)") (class "Default")
      (node (ref "R11") (pin "P$2") (pinfunction "P$2_P$2") (pintype "passive"))
      (node (ref "R12") (pin "P$1") (pinfunction "P$1_P$1") (pintype "passive"))
      (node (ref "U4") (pin "1") (pinfunction "FB_1") (pintype "bidirectional"))
    )
    (net (code "63") (name "Net-(U4-SHDN)") (class "Default")
      (node (ref "R10") (pin "P$1") (pinfunction "P$1_P$1") (pintype "passive"))
      (node (ref "U4") (pin "48") (pinfunction "SHDN_48") (pintype "bidirectional"))
    )
    (net (code "64") (name "Net-(U4-SW)") (class "Default")
      (node (ref "C20") (pin "P$2") (pinfunction "P$2_P$2") (pintype "passive"))
      (node (ref "D1") (pin "CATHODE") (pinfunction "CATHODE_CATHODE") (pintype "bidirectional"))
      (node (ref "L1") (pin "2") (pinfunction "2_2") (pintype "passive"))
      (node (ref "U4") (pin "45") (pinfunction "SW_45") (pintype "bidirectional"))
    )
    (net (code "65") (name "Net-(U4-VCP)") (class "Default")
      (node (ref "C15") (pin "P$2") (pinfunction "P$2_P$2") (pintype "passive"))
      (node (ref "U4") (pin "5") (pinfunction "VCP_5") (pintype "bidirectional"))
    )
    (net (code "66") (name "V+") (class "Default")
      (node (ref "C14") (pin "P$1") (pinfunction "P$1_P$1") (pintype "passive"))
      (node (ref "C15") (pin "P$1") (pinfunction "P$1_P$1") (pintype "passive"))
      (node (ref "C19") (pin "P$1") (pinfunction "P$1_P$1") (pintype "passive"))
      (node (ref "C22") (pin "P$1") (pinfunction "P$1_P$1") (pintype "passive"))
      (node (ref "C23") (pin "P$1") (pinfunction "P$1_P$1") (pintype "passive"))
      (node (ref "C24") (pin "P$1") (pinfunction "P$1_P$1") (pintype "passive"))
      (node (ref "C25") (pin "P$1") (pinfunction "P$1_P$1") (pintype "passive"))
      (node (ref "C26") (pin "P$1") (pinfunction "P$1_P$1") (pintype "passive"))
      (node (ref "C27") (pin "P$1") (pinfunction "P$1_P$1") (pintype "passive"))
      (node (ref "C28") (pin "P$1") (pinfunction "P$1_P$1") (pintype "passive"))
      (node (ref "C29") (pin "P$1") (pinfunction "P$1_P$1") (pintype "passive"))
      (node (ref "C30") (pin "P$1") (pinfunction "P$1_P$1") (pintype "passive"))
      (node (ref "C31") (pin "P$1") (pinfunction "P$1_P$1") (pintype "passive"))
      (node (ref "C32") (pin "P$1") (pinfunction "P$1_P$1") (pintype "passive"))
      (node (ref "C33") (pin "P$1") (pinfunction "P$1_P$1") (pintype "passive"))
      (node (ref "C34") (pin "P$1") (pinfunction "P$1_P$1") (pintype "passive"))
      (node (ref "C35") (pin "P$1") (pinfunction "P$1_P$1") (pintype "passive"))
      (node (ref "C36") (pin "P$1") (pinfunction "P$1_P$1") (pintype "passive"))
      (node (ref "C37") (pin "P$1") (pinfunction "P$1_P$1") (pintype "passive"))
      (node (ref "J1") (pin "1") (pinfunction "1_1") (pintype "passive"))
      (node (ref "J2") (pin "1") (pinfunction "1_1") (pintype "passive"))
      (node (ref "Q1") (pin "5") (pinfunction "D_5") (pintype "passive"))
      (node (ref "Q1") (pin "6") (pinfunction "D_6") (pintype "passive"))
      (node (ref "Q1") (pin "7") (pinfunction "D_7") (pintype "passive"))
      (node (ref "Q1") (pin "8") (pinfunction "D_8") (pintype "passive"))
      (node (ref "Q1") (pin "PAD") (pinfunction "D_PAD") (pintype "passive"))
      (node (ref "Q3") (pin "5") (pinfunction "D_5") (pintype "passive"))
      (node (ref "Q3") (pin "6") (pinfunction "D_6") (pintype "passive"))
      (node (ref "Q3") (pin "7") (pinfunction "D_7") (pintype "passive"))
      (node (ref "Q3") (pin "8") (pinfunction "D_8") (pintype "passive"))
      (node (ref "Q3") (pin "PAD") (pinfunction "D_PAD") (pintype "passive"))
      (node (ref "Q5") (pin "5") (pinfunction "D_5") (pintype "passive"))
      (node (ref "Q5") (pin "6") (pinfunction "D_6") (pintype "passive"))
      (node (ref "Q5") (pin "7") (pinfunction "D_7") (pintype "passive"))
      (node (ref "Q5") (pin "8") (pinfunction "D_8") (pintype "passive"))
      (node (ref "Q5") (pin "PAD") (pinfunction "D_PAD") (pintype "passive"))
      (node (ref "R10") (pin "P$2") (pinfunction "P$2_P$2") (pintype "passive"))
      (node (ref "R5") (pin "P$2") (pinfunction "P$2_P$2") (pintype "passive"))
      (node (ref "U4") (pin "47") (pinfunction "VIN_47") (pintype "bidirectional"))
      (node (ref "U4") (pin "6") (pinfunction "VM_6") (pintype "bidirectional"))
      (node (ref "U4") (pin "7") (pinfunction "VDRAIN_7") (pintype "bidirectional"))
    )
    (net (code "67") (name "V-") (class "Default")
      (node (ref "C14") (pin "P$2") (pinfunction "P$2_P$2") (pintype "passive"))
      (node (ref "C19") (pin "P$2") (pinfunction "P$2_P$2") (pintype "passive"))
      (node (ref "C22") (pin "P$2") (pinfunction "P$2_P$2") (pintype "passive"))
      (node (ref "C23") (pin "P$2") (pinfunction "P$2_P$2") (pintype "passive"))
      (node (ref "C24") (pin "P$2") (pinfunction "P$2_P$2") (pintype "passive"))
      (node (ref "C25") (pin "P$2") (pinfunction "P$2_P$2") (pintype "passive"))
      (node (ref "C26") (pin "P$2") (pinfunction "P$2_P$2") (pintype "passive"))
      (node (ref "C27") (pin "P$2") (pinfunction "P$2_P$2") (pintype "passive"))
      (node (ref "C28") (pin "P$2") (pinfunction "P$2_P$2") (pintype "passive"))
      (node (ref "C29") (pin "P$2") (pinfunction "P$2_P$2") (pintype "passive"))
      (node (ref "C30") (pin "P$2") (pinfunction "P$2_P$2") (pintype "passive"))
      (node (ref "C31") (pin "P$2") (pinfunction "P$2_P$2") (pintype "passive"))
      (node (ref "C32") (pin "P$2") (pinfunction "P$2_P$2") (pintype "passive"))
      (node (ref "C33") (pin "P$2") (pinfunction "P$2_P$2") (pintype "passive"))
      (node (ref "C34") (pin "P$2") (pinfunction "P$2_P$2") (pintype "passive"))
      (node (ref "C35") (pin "P$2") (pinfunction "P$2_P$2") (pintype "passive"))
      (node (ref "C36") (pin "P$2") (pinfunction "P$2_P$2") (pintype "passive"))
      (node (ref "C37") (pin "P$2") (pinfunction "P$2_P$2") (pintype "passive"))
      (node (ref "D1") (pin "ANODE") (pinfunction "ANODE_ANODE") (pintype "bidirectional"))
      (node (ref "J1") (pin "2") (pinfunction "2_2") (pintype "passive"))
      (node (ref "J2") (pin "2") (pinfunction "2_2") (pintype "passive"))
      (node (ref "R12") (pin "P$2") (pinfunction "P$2_P$2") (pintype "passive"))
      (node (ref "RA") (pin "1") (pinfunction "1_1") (pintype "passive"))
      (node (ref "RB") (pin "1") (pinfunction "1_1") (pintype "passive"))
      (node (ref "RC") (pin "1") (pinfunction "1_1") (pintype "passive"))
      (node (ref "SH1") (pin "2") (pinfunction "P$2_2") (pintype "bidirectional"))
      (node (ref "SH2") (pin "2") (pinfunction "P$2_2") (pintype "bidirectional"))
      (node (ref "SH3") (pin "2") (pinfunction "P$2_2") (pintype "bidirectional"))
      (node (ref "SH4") (pin "1") (pinfunction "P$1_1") (pintype "bidirectional"))
      (node (ref "U4") (pin "2") (pinfunction "PGND_2") (pintype "bidirectional"))
      (node (ref "U4") (pin "43") (pinfunction "BGND_43") (pintype "bidirectional"))
      (node (ref "U4") (pin "P1") (pinfunction "PAD_P1") (pintype "bidirectional"))
      (node (ref "U4") (pin "P10") (pinfunction "PAD_P10") (pintype "bidirectional"))
      (node (ref "U4") (pin "P11") (pinfunction "PAD_P11") (pintype "bidirectional"))
      (node (ref "U4") (pin "P12") (pinfunction "PAD_P12") (pintype "bidirectional"))
      (node (ref "U4") (pin "P13") (pinfunction "PAD_P13") (pintype "bidirectional"))
      (node (ref "U4") (pin "P14") (pinfunction "PAD_P14") (pintype "bidirectional"))
      (node (ref "U4") (pin "P15") (pinfunction "PAD_P15") (pintype "bidirectional"))
      (node (ref "U4") (pin "P16") (pinfunction "PAD_P16") (pintype "bidirectional"))
      (node (ref "U4") (pin "P17") (pinfunction "PAD_P17") (pintype "bidirectional"))
      (node (ref "U4") (pin "P18") (pinfunction "PAD_P18") (pintype "bidirectional"))
      (node (ref "U4") (pin "P19") (pinfunction "PAD_P19") (pintype "bidirectional"))
      (node (ref "U4") (pin "P2") (pinfunction "PAD_P2") (pintype "bidirectional"))
      (node (ref "U4") (pin "P20") (pinfunction "PAD_P20") (pintype "bidirectional"))
      (node (ref "U4") (pin "P21") (pinfunction "PAD_P21") (pintype "bidirectional"))
      (node (ref "U4") (pin "P22") (pinfunction "PAD_P22") (pintype "bidirectional"))
      (node (ref "U4") (pin "P23") (pinfunction "PAD_P23") (pintype "bidirectional"))
      (node (ref "U4") (pin "P24") (pinfunction "PAD_P24") (pintype "bidirectional"))
      (node (ref "U4") (pin "P25") (pinfunction "PAD_P25") (pintype "bidirectional"))
      (node (ref "U4") (pin "P3") (pinfunction "PAD_P3") (pintype "bidirectional"))
      (node (ref "U4") (pin "P4") (pinfunction "PAD_P4") (pintype "bidirectional"))
      (node (ref "U4") (pin "P5") (pinfunction "PAD_P5") (pintype "bidirectional"))
      (node (ref "U4") (pin "P6") (pinfunction "PAD_P6") (pintype "bidirectional"))
      (node (ref "U4") (pin "P7") (pinfunction "PAD_P7") (pintype "bidirectional"))
      (node (ref "U4") (pin "P8") (pinfunction "PAD_P8") (pintype "bidirectional"))
      (node (ref "U4") (pin "P9") (pinfunction "PAD_P9") (pintype "bidirectional"))
      (node (ref "U4") (pin "PAD") (pinfunction "PAD_PAD") (pintype "bidirectional"))
    )
    (net (code "68") (name "unconnected-(SWD-Pad1)") (class "Default")
      (node (ref "SWD") (pin "1") (pinfunction "1_1") (pintype "passive"))
    )
    (net (code "69") (name "unconnected-(U1-PA10-Pad32)") (class "Default")
      (node (ref "U1") (pin "32") (pinfunction "PA10_32") (pintype "bidirectional"))
    )
    (net (code "70") (name "unconnected-(U1-PA15-Pad38)") (class "Default")
      (node (ref "U1") (pin "38") (pinfunction "PA15_38") (pintype "bidirectional"))
    )
    (net (code "71") (name "unconnected-(U1-PB3-Pad41)") (class "Default")
      (node (ref "U1") (pin "41") (pinfunction "PB3_41") (pintype "bidirectional"))
    )
    (net (code "72") (name "unconnected-(U1-PB10-Pad22)") (class "Default")
      (node (ref "U1") (pin "22") (pinfunction "PB10_22") (pintype "bidirectional"))
    )
    (net (code "73") (name "unconnected-(U1-PC6-Pad29)") (class "Default")
      (node (ref "U1") (pin "29") (pinfunction "PC6_29") (pintype "bidirectional"))
    )
    (net (code "74") (name "unconnected-(U1-PC13-Pad2)") (class "Default")
      (node (ref "U1") (pin "2") (pinfunction "PC13_2") (pintype "bidirectional"))
    )
    (net (code "75") (name "unconnected-(U3-I-Pad14)") (class "Default")
      (node (ref "U3") (pin "14") (pinfunction "I_14") (pintype "bidirectional"))
    )
    (net (code "76") (name "unconnected-(U3-PWM-Pad8)") (class "Default")
      (node (ref "U3") (pin "8") (pinfunction "PWM_8") (pintype "bidirectional"))
    )
    (net (code "77") (name "unconnected-(U3-VDD5V-Pad11)") (class "Default")
      (node (ref "U3") (pin "11") (pinfunction "VDD5V_11") (pintype "bidirectional"))
    )
    (net (code "78") (name "unconnected-(U4-CAL-Pad34)") (class "Default")
      (node (ref "U4") (pin "34") (pinfunction "CAL_34") (pintype "bidirectional"))
    )
  )
)
